# ProProject_ExtBoard-002_2024-05-18.net
KiCad netlist of a schematic drawn in EasyEDA Pro
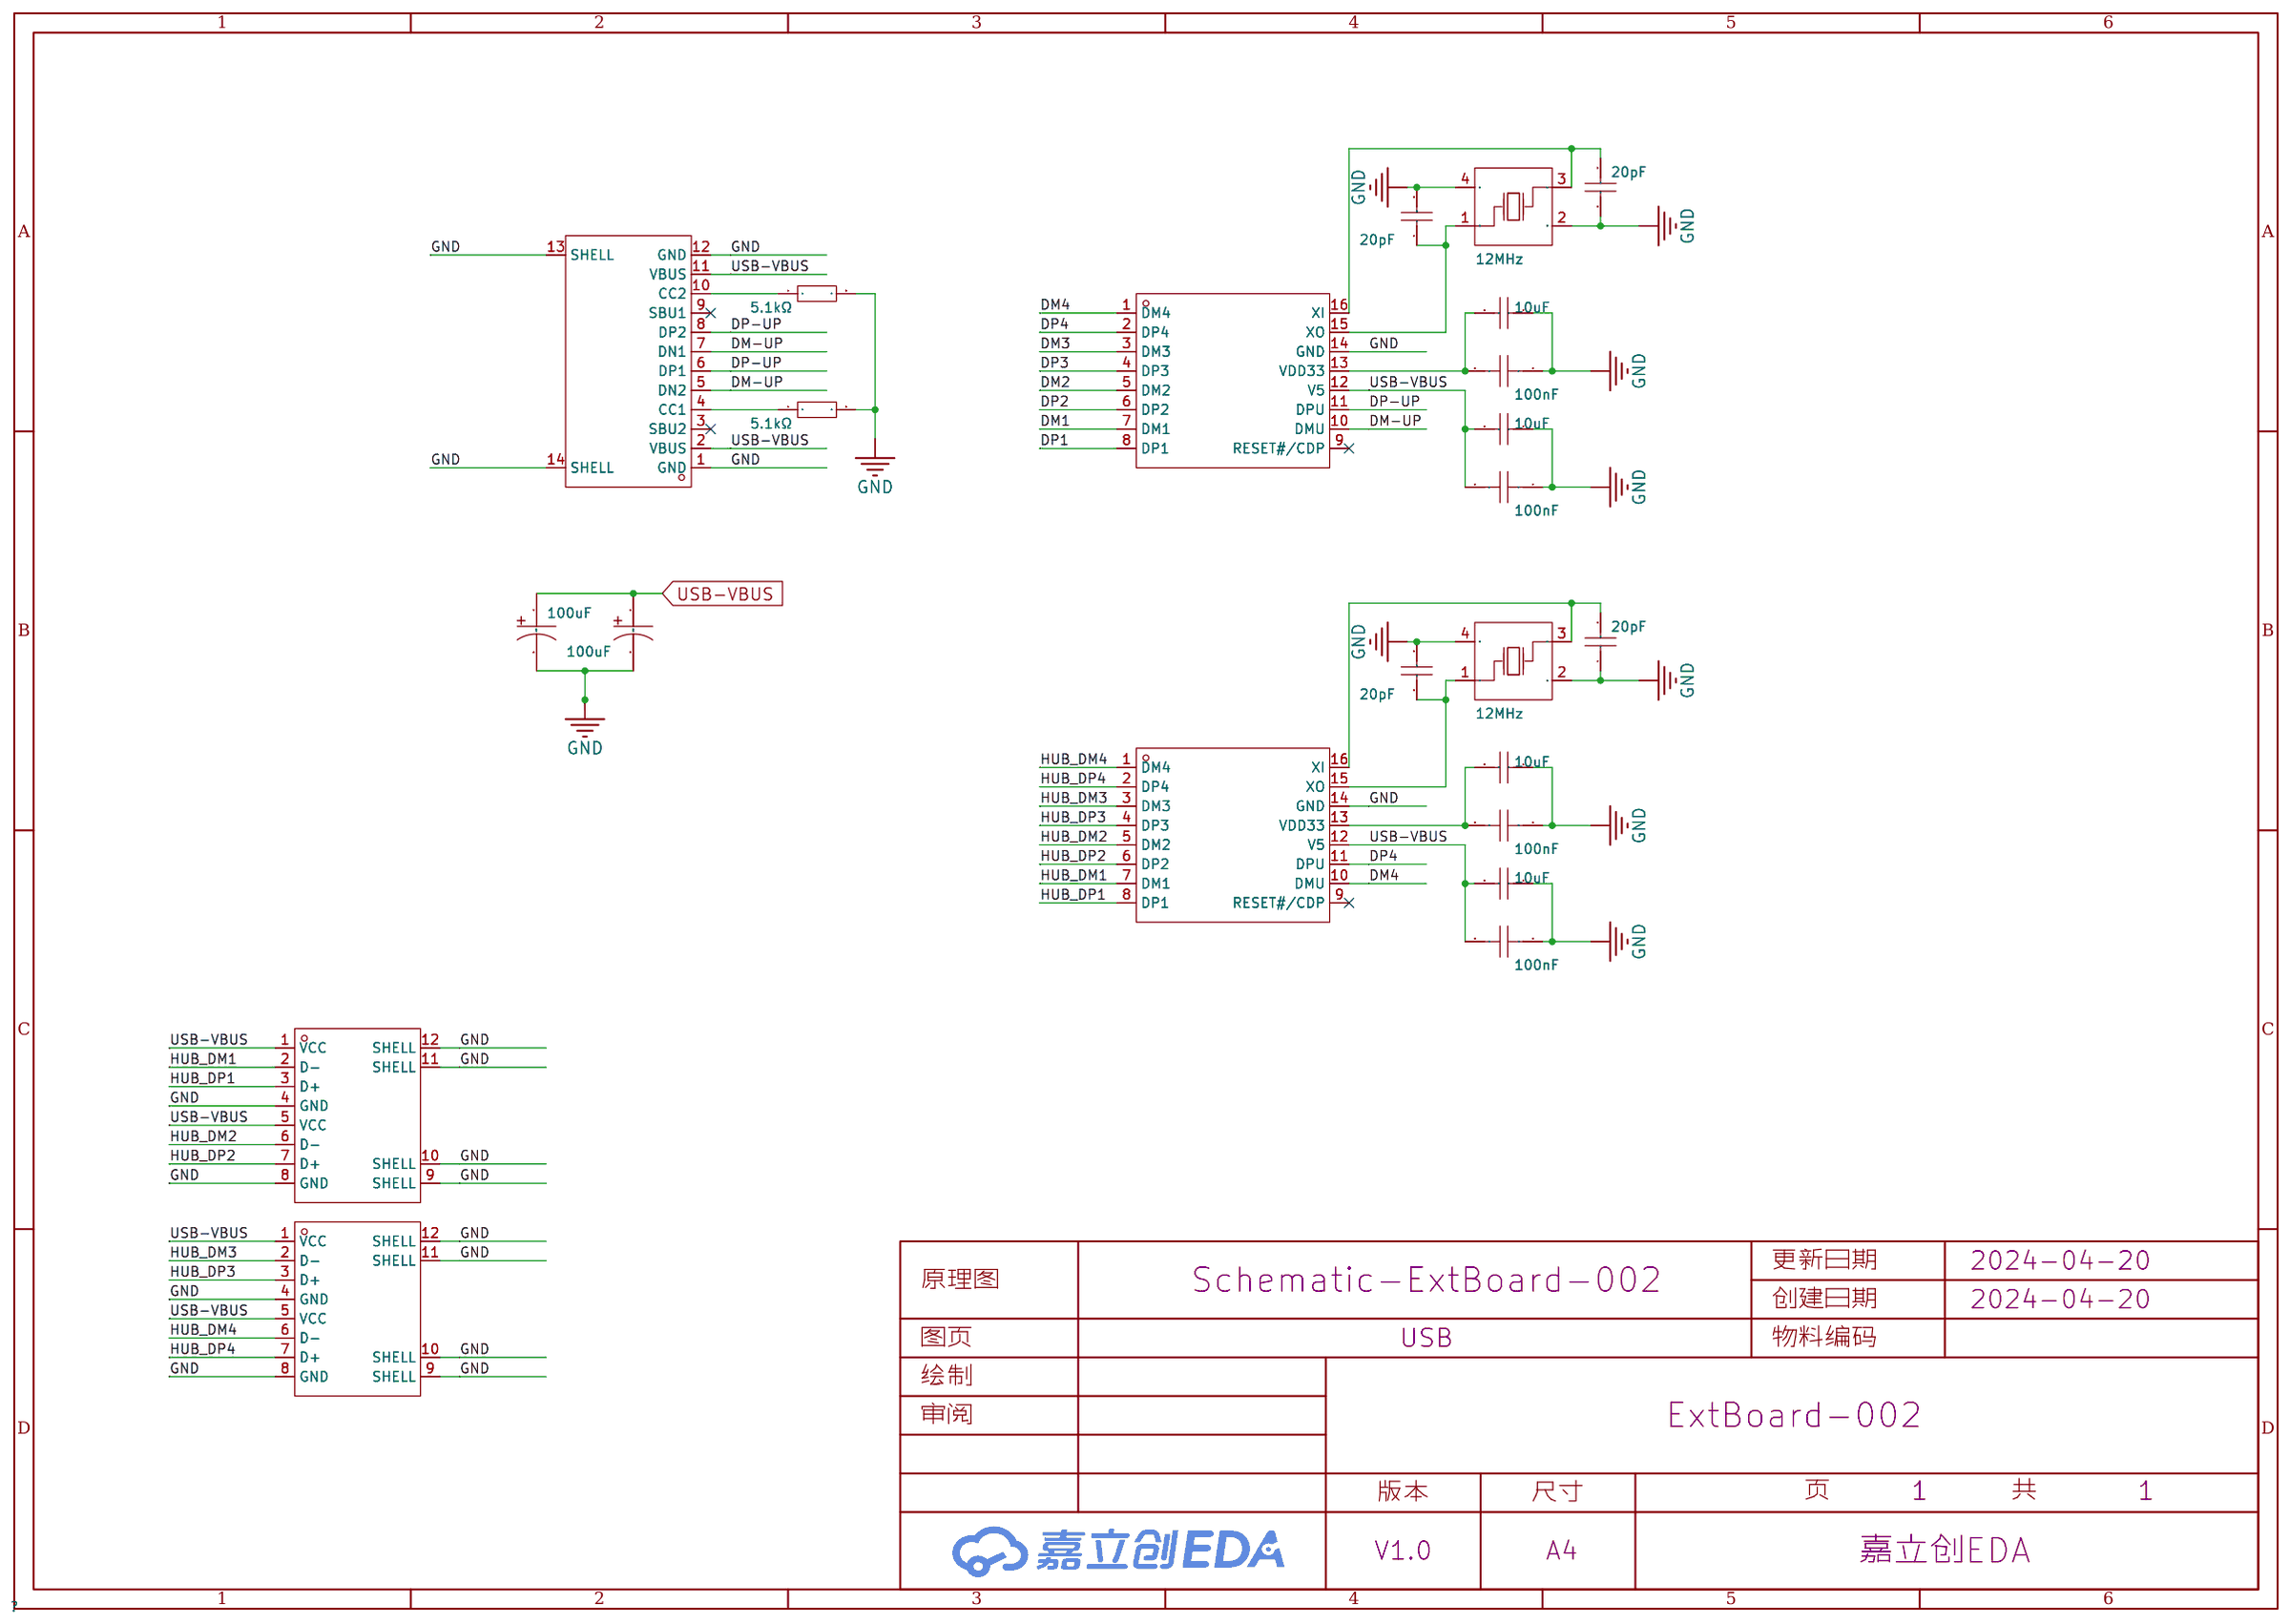
[diagram p0: USB]
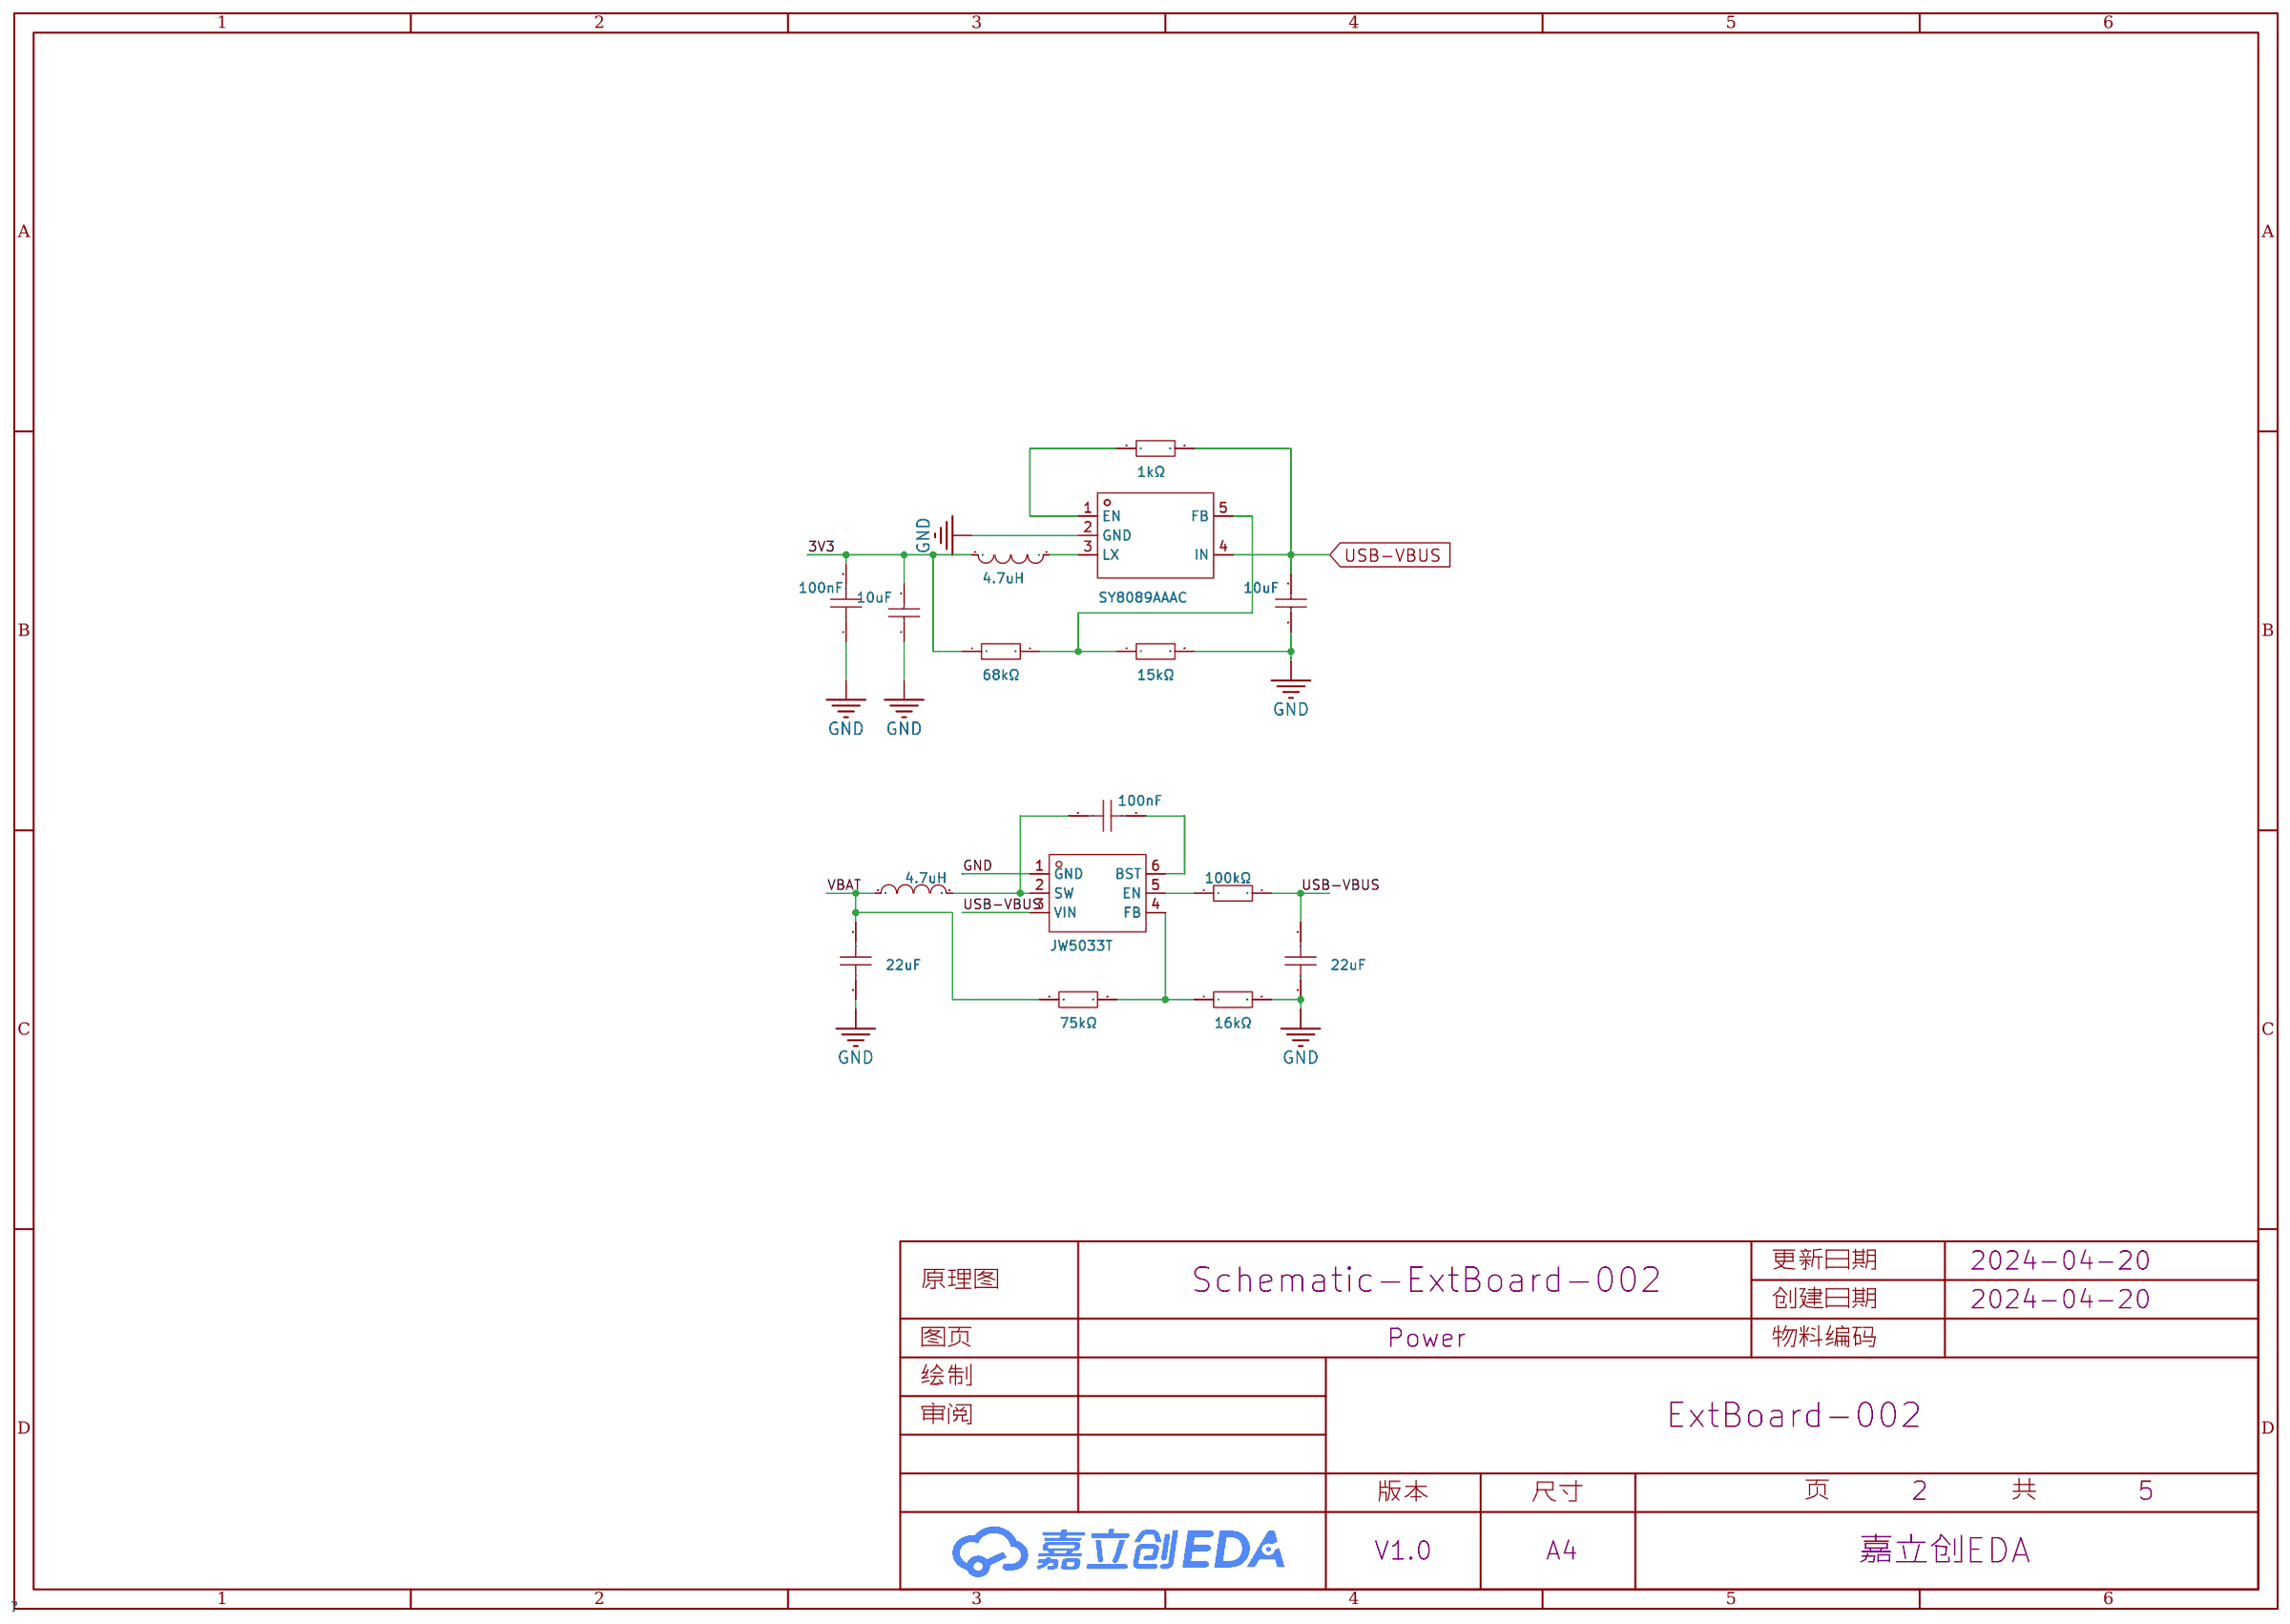
[diagram p1: Power]
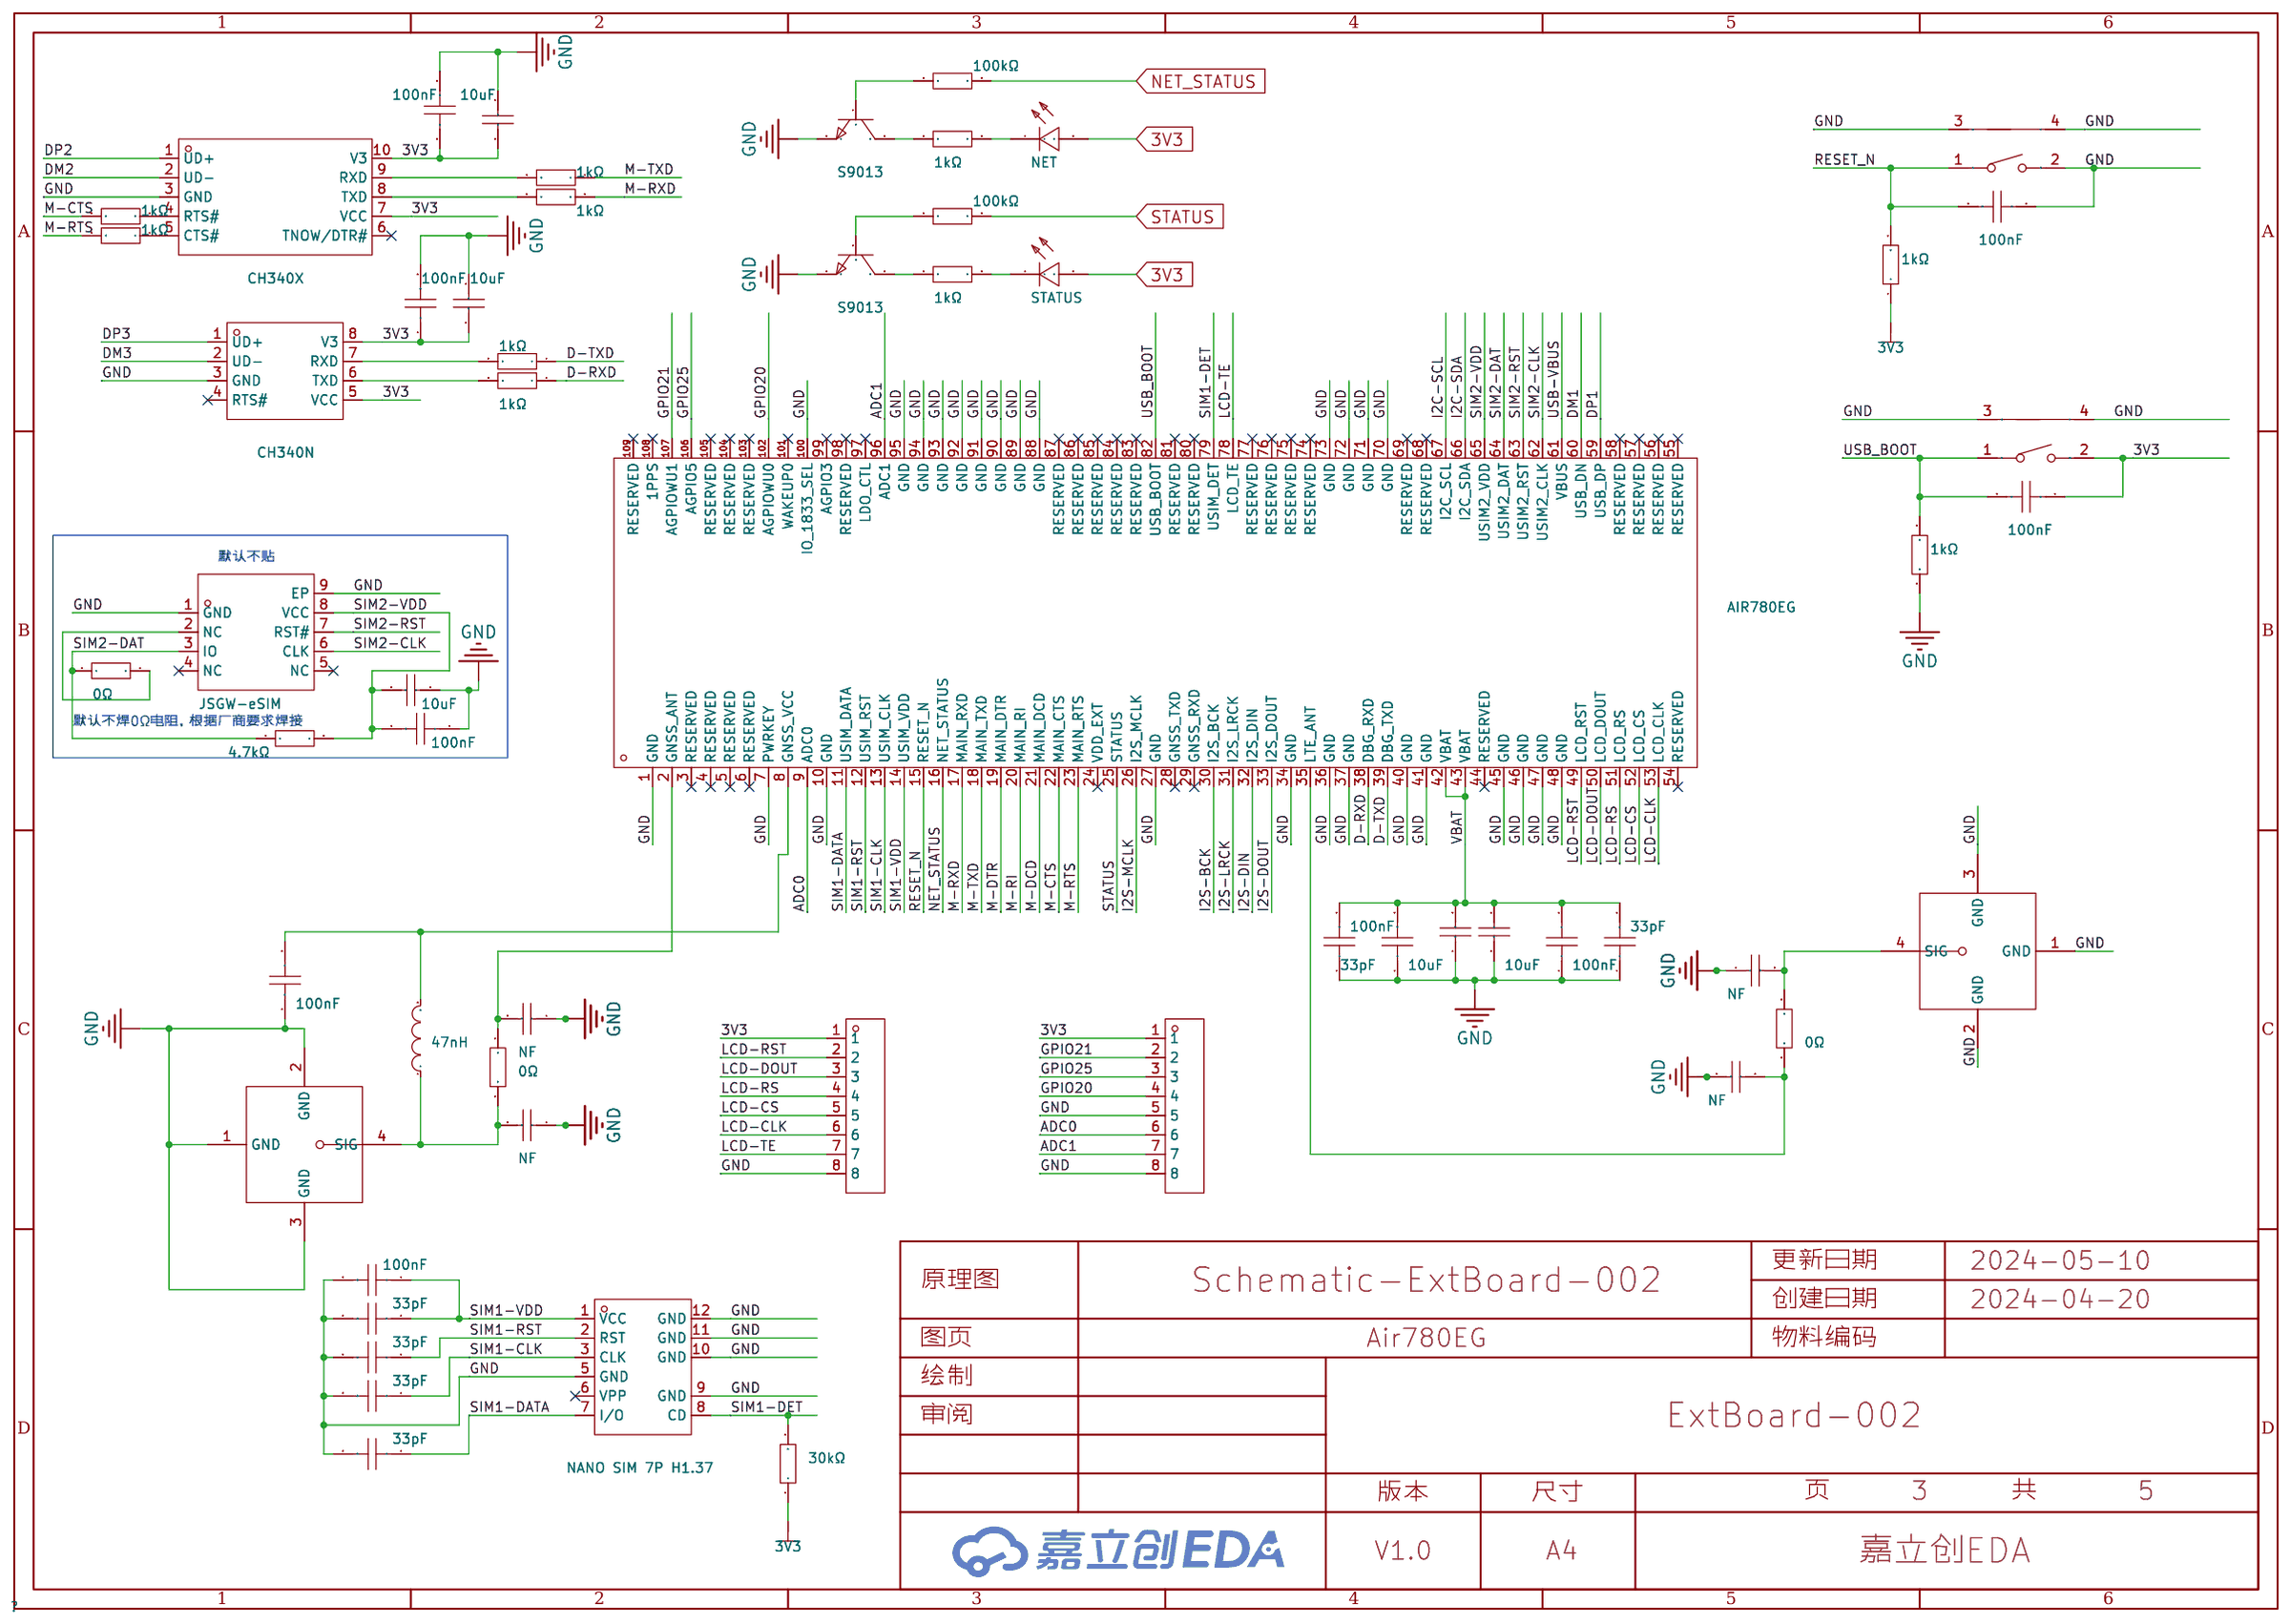
[diagram p2: Air780EG]
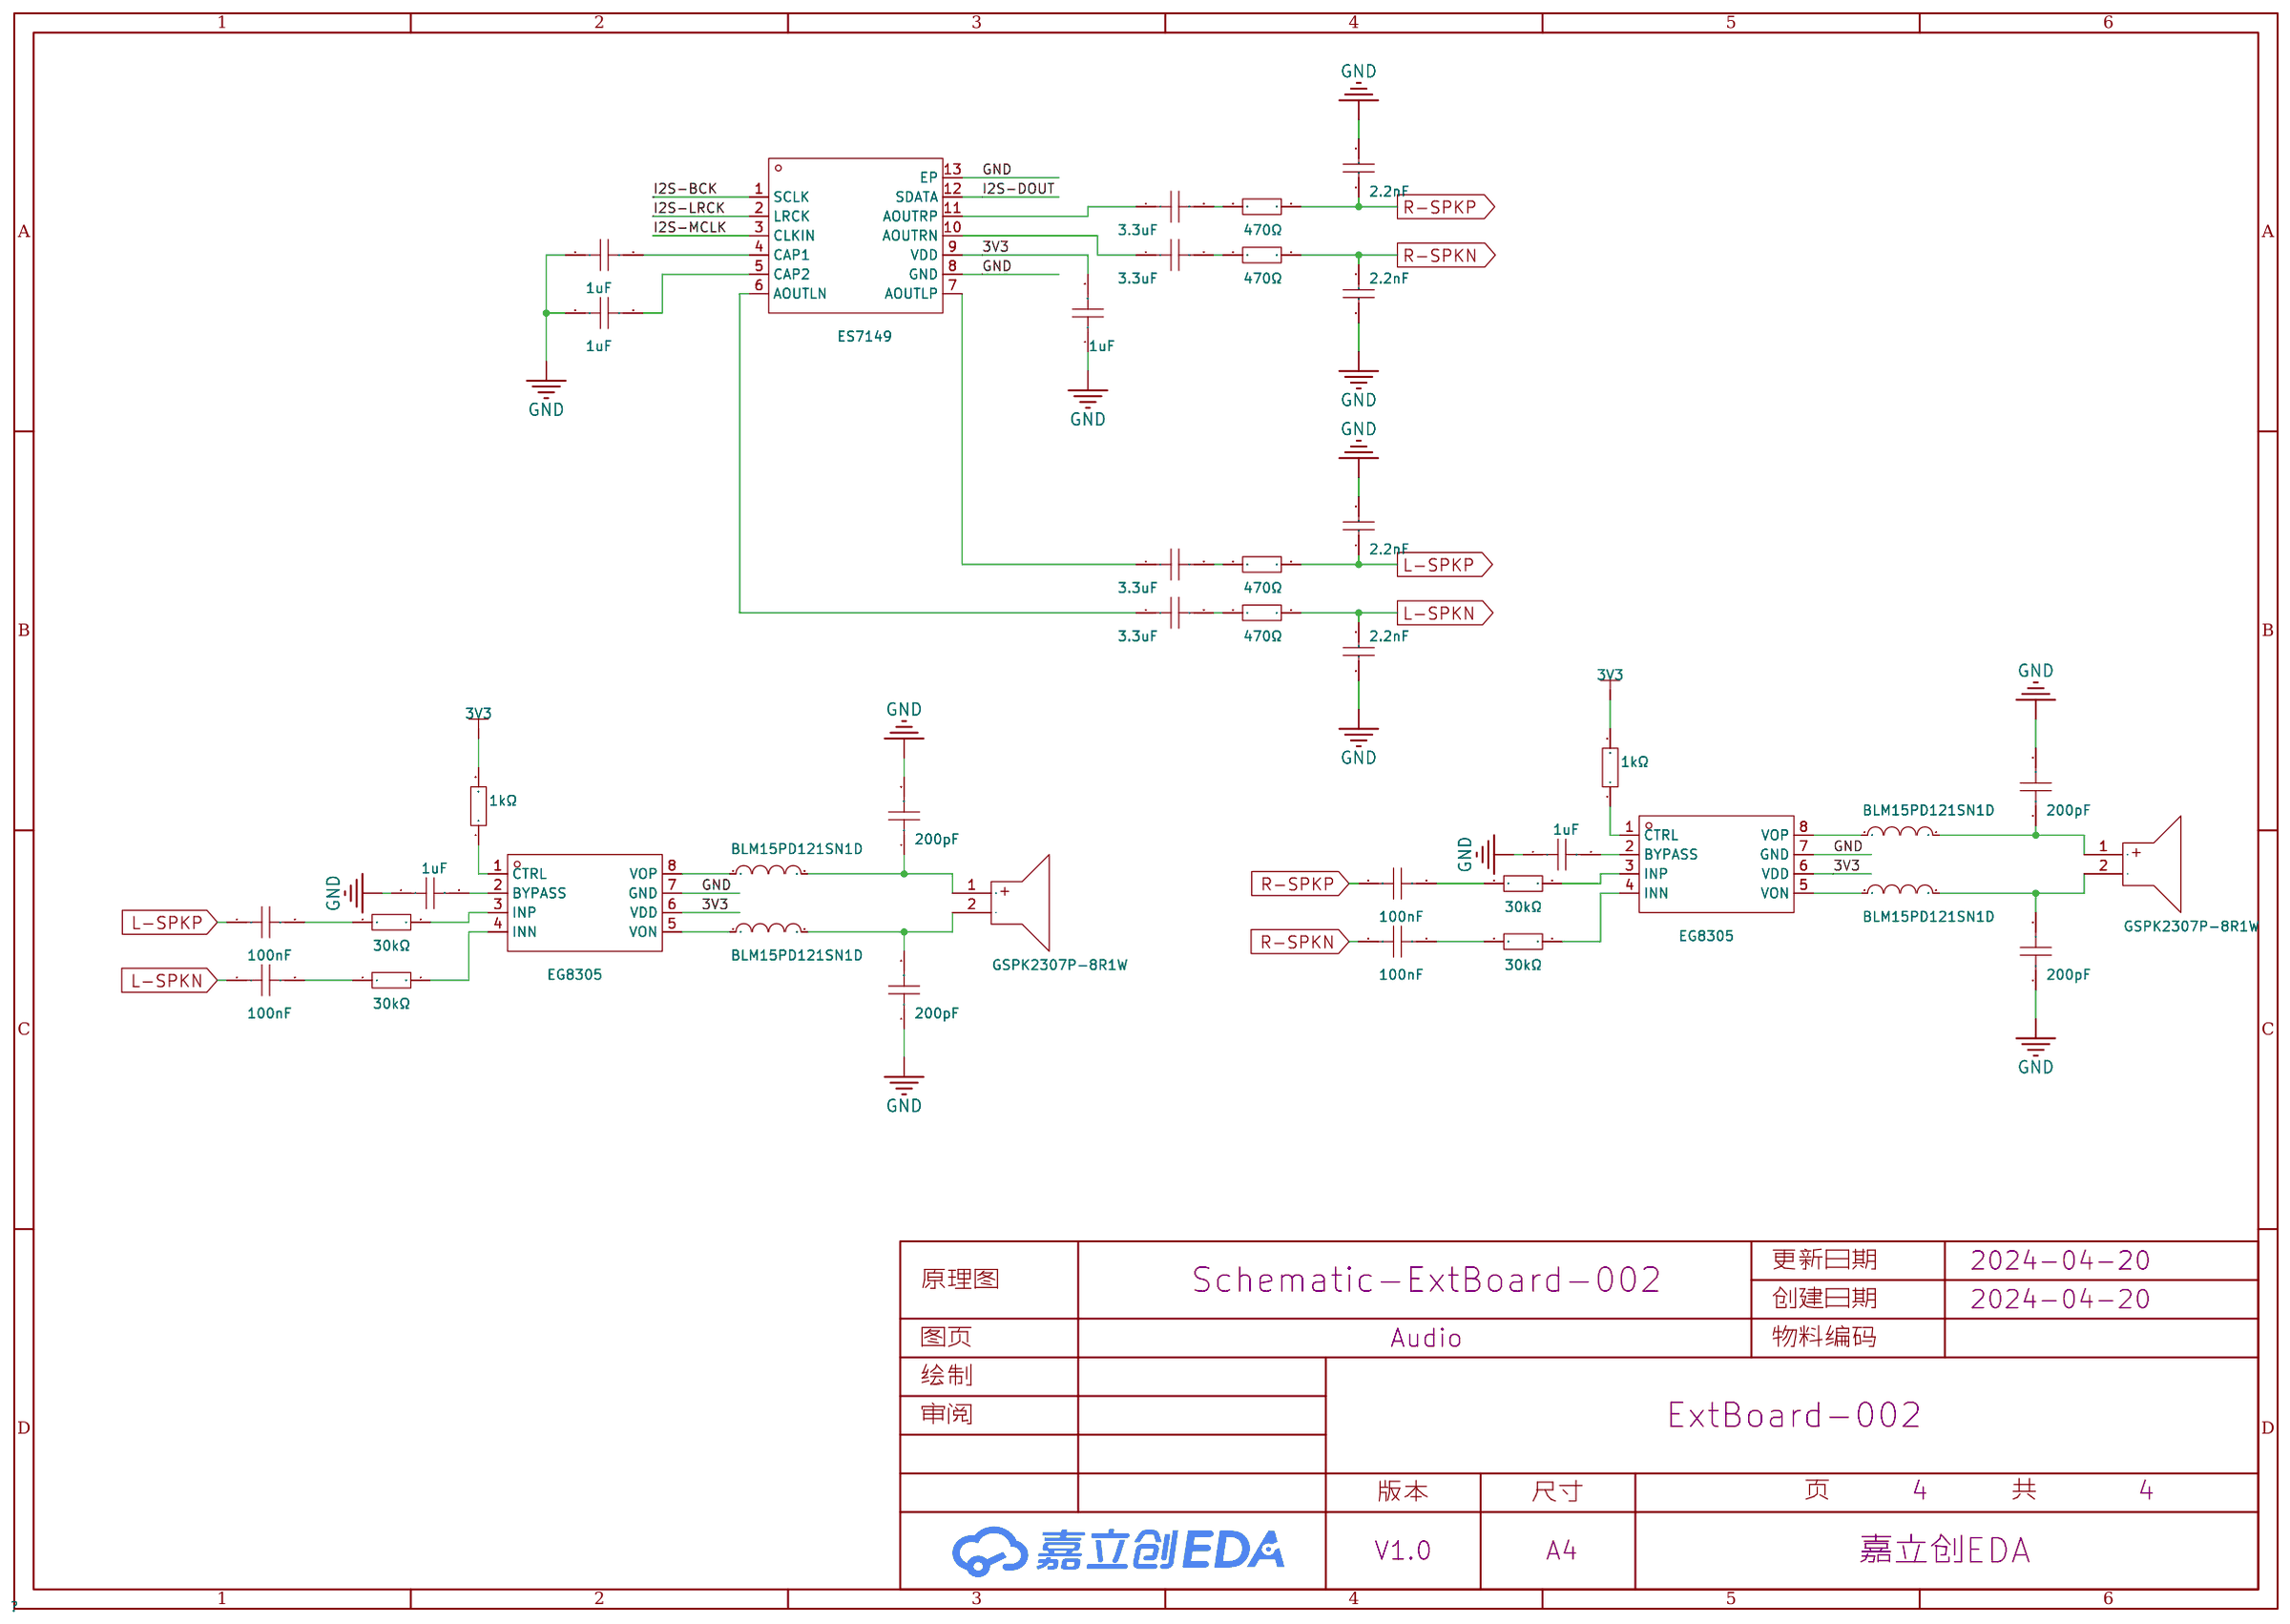
[diagram p3: Audio]
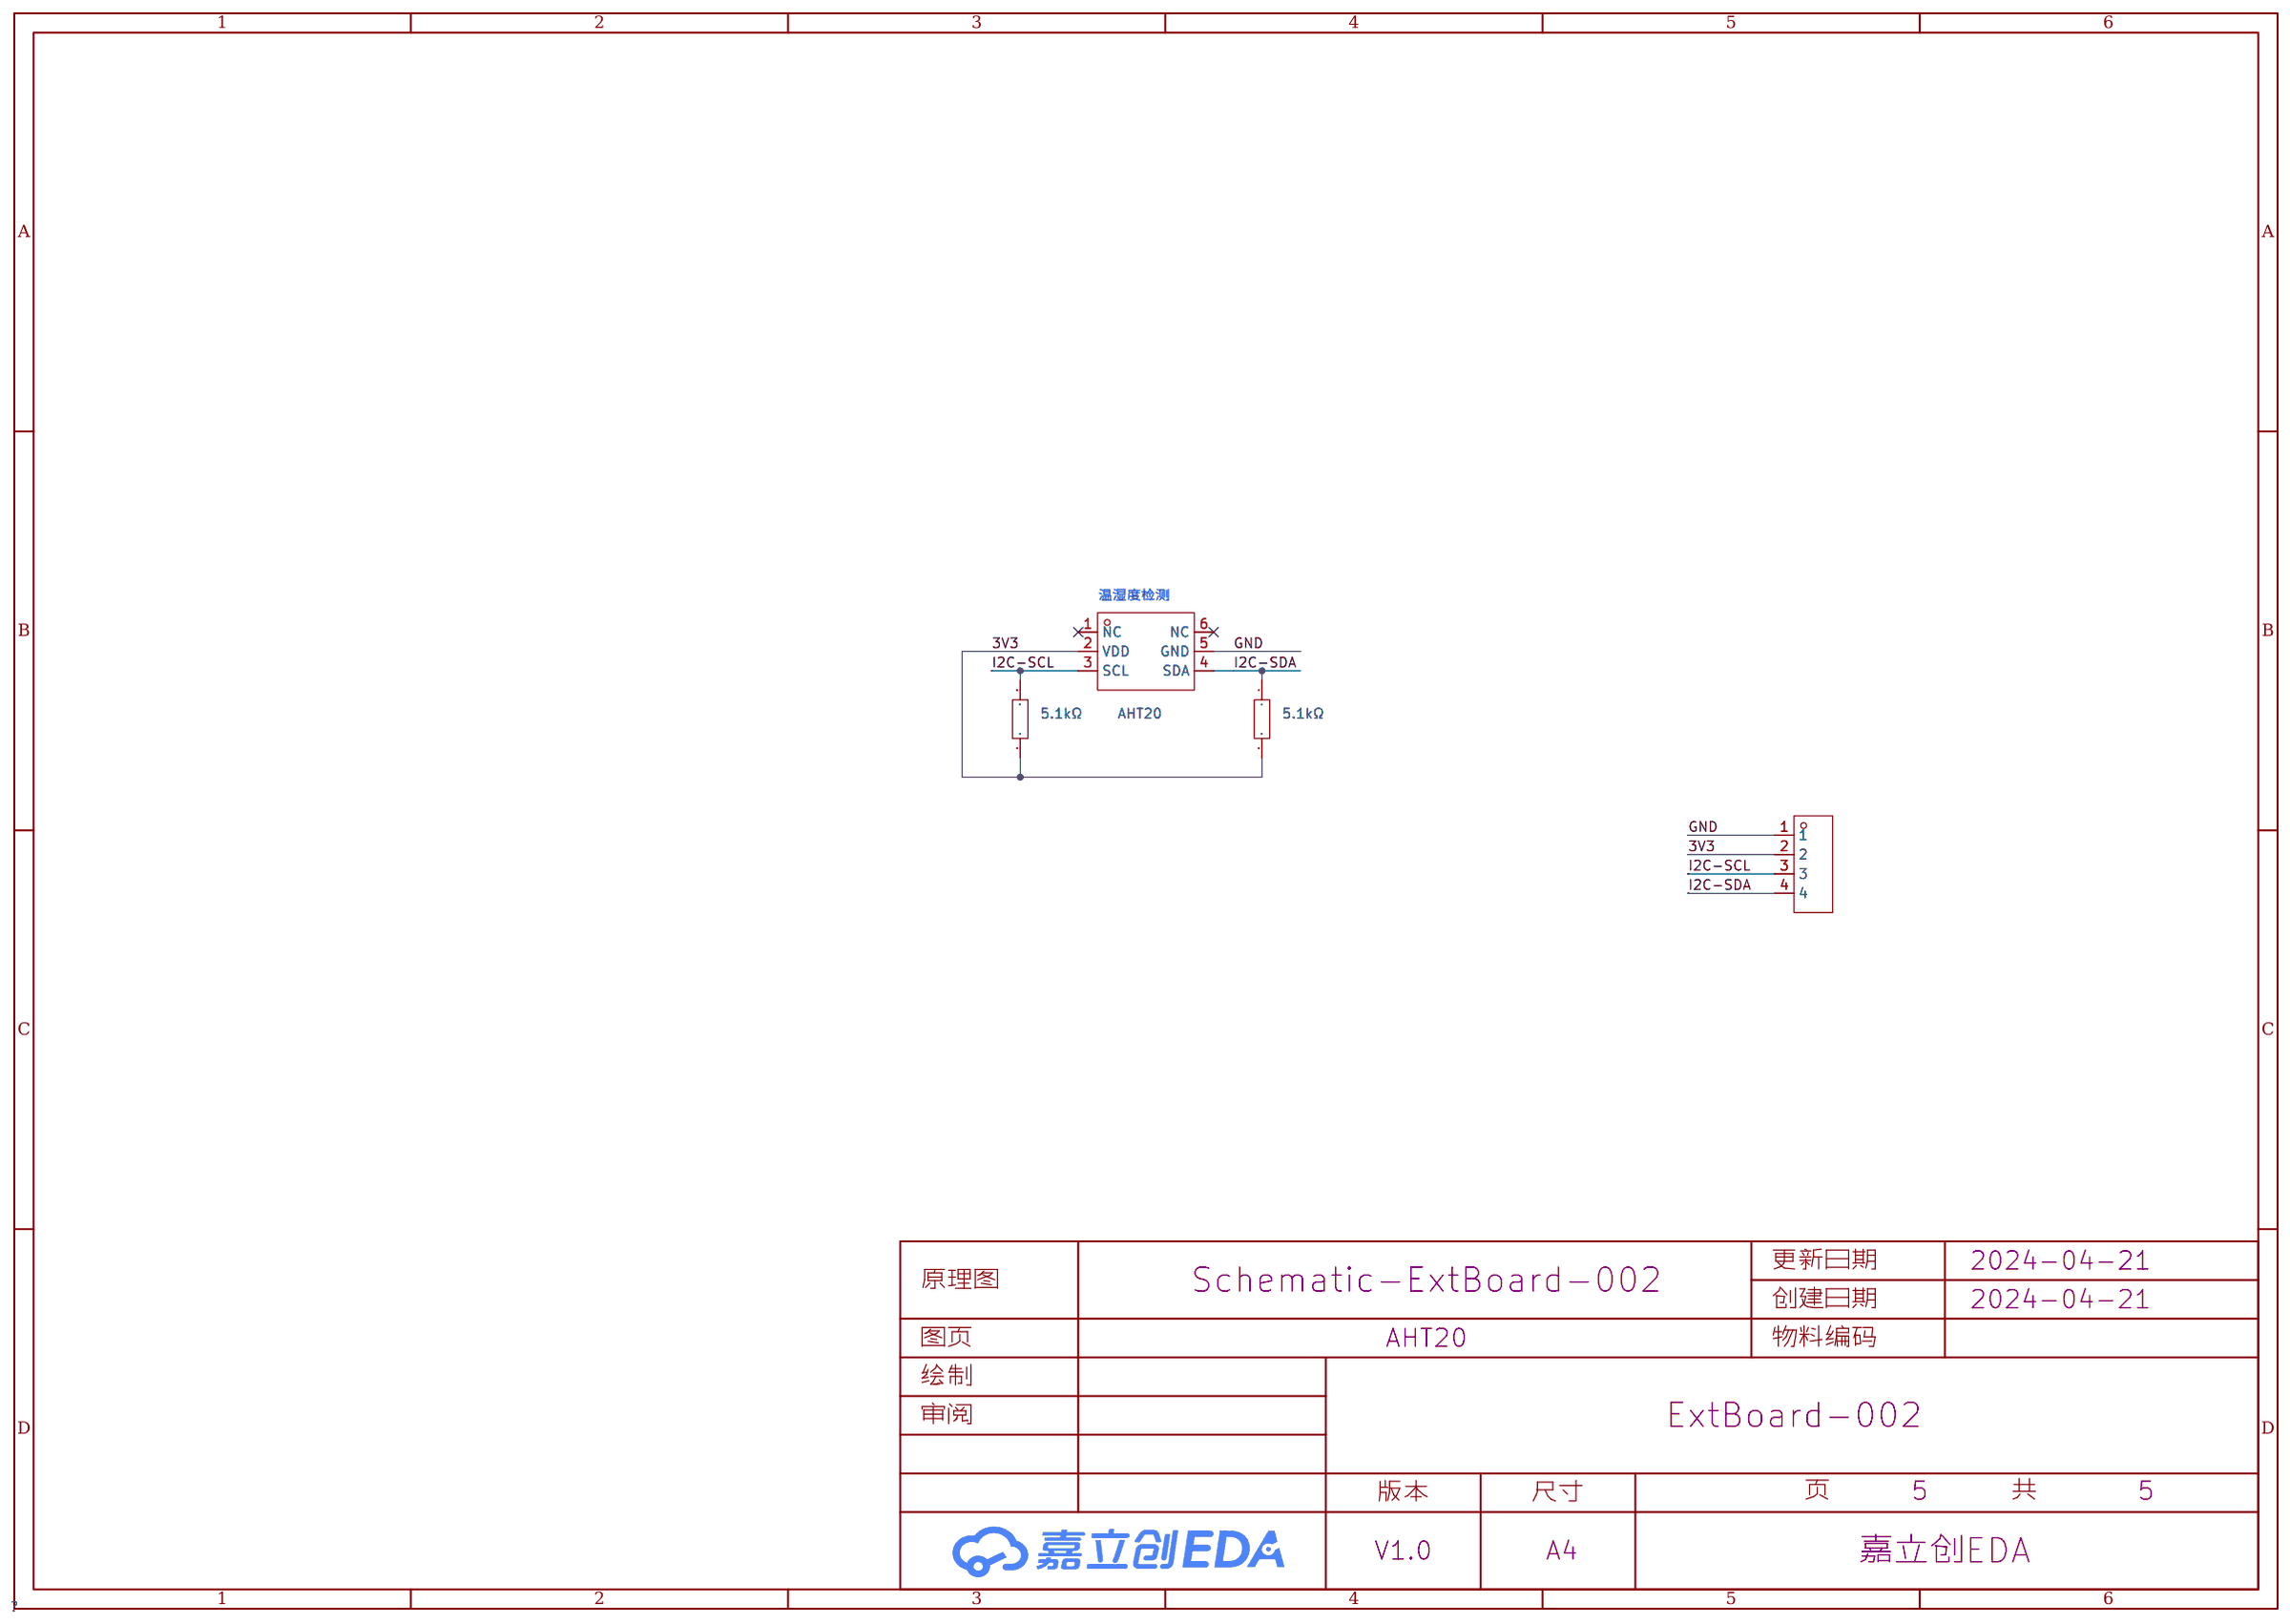
[diagram p4: AHT20]

(export (version "E")
  (design (tool "Eeschema 10.0.6"))
  (components
    (comp (ref "C1")
      (value "20pF")
      (footprint "easyedapro:C0402")
      (description "容值:20pF;精度:±5%;额定电压:50V;材质(温度系数):C0G;")
      (fields (field (name "Manufacturer Part") "0402CG200J500NT") (field (name "Manufacturer") "FH(风华)"))
      (libsource (lib "easyedapro") (part "0402CG200J500NT"))
    )
    (comp (ref "C2")
      (value "20pF")
      (footprint "easyedapro:C0402")
      (description "容值:20pF;精度:±5%;额定电压:50V;材质(温度系数):C0G;")
      (fields (field (name "Manufacturer Part") "0402CG200J500NT") (field (name "Manufacturer") "FH(风华)"))
      (libsource (lib "easyedapro") (part "0402CG200J500NT"))
    )
    (comp (ref "C3")
      (value "10uF")
      (footprint "easyedapro:C0402")
      (description "容值:10uF;精度:±20%;额定电压:6.3V;材质(温度系数):X5R;")
      (fields
        (field (name "Manufacturer Part") "CL05A106MQ5NUNC")
        (field (name "Manufacturer") "SAMSUNG(三星)")
      )
      (libsource (lib "easyedapro") (part "CL05A106MQ5NUNC"))
    )
    (comp (ref "C4")
      (value "100nF")
      (footprint "easyedapro:C0402")
      (description "容值:100nF;精度:±10%;额定电压:16V;材质(温度系数):X7R;")
      (fields
        (field (name "Manufacturer Part") "CC0402KRX7R7BB104")
        (field (name "Manufacturer") "YAGEO(国巨)")
      )
      (libsource (lib "easyedapro") (part "CC0402KRX7R7BB104"))
    )
    (comp (ref "C5")
      (value "10uF")
      (footprint "easyedapro:C0402")
      (description "容值:10uF;精度:±20%;额定电压:6.3V;材质(温度系数):X5R;")
      (fields
        (field (name "Manufacturer Part") "CL05A106MQ5NUNC")
        (field (name "Manufacturer") "SAMSUNG(三星)")
      )
      (libsource (lib "easyedapro") (part "CL05A106MQ5NUNC"))
    )
    (comp (ref "C6")
      (value "100nF")
      (footprint "easyedapro:C0402")
      (description "容值:100nF;精度:±10%;额定电压:16V;材质(温度系数):X7R;")
      (fields
        (field (name "Manufacturer Part") "CC0402KRX7R7BB104")
        (field (name "Manufacturer") "YAGEO(国巨)")
      )
      (libsource (lib "easyedapro") (part "CC0402KRX7R7BB104"))
    )
    (comp (ref "C7")
      (value "100uF")
      (footprint "easyedapro:CAP-SMD_BD6.3-L6.6-W6.6-FD")
      (description "容值:100uF;精度:±20%;额定电压:16V;纹波电流:-;等效串联电阻:-;")
      (fields (field (name "Manufacturer Part") "VEZ101M1CTR-0605") (field (name "Manufacturer") "lelon(立隆)"))
      (libsource (lib "easyedapro") (part "VEZ101M1C0605-TRO"))
    )
    (comp (ref "C8")
      (value "100uF")
      (footprint "easyedapro:CAP-SMD_BD6.3-L6.6-W6.6-FD")
      (description "容值:100uF;精度:±20%;额定电压:16V;纹波电流:-;等效串联电阻:-;")
      (fields (field (name "Manufacturer Part") "VEZ101M1CTR-0605") (field (name "Manufacturer") "lelon(立隆)"))
      (libsource (lib "easyedapro") (part "VEZ101M1C0605-TRO"))
    )
    (comp (ref "C9")
      (value "20pF")
      (footprint "easyedapro:C0402")
      (description "容值:20pF;精度:±5%;额定电压:50V;材质(温度系数):C0G;")
      (fields (field (name "Manufacturer Part") "0402CG200J500NT") (field (name "Manufacturer") "FH(风华)"))
      (libsource (lib "easyedapro") (part "0402CG200J500NT"))
    )
    (comp (ref "C10")
      (value "20pF")
      (footprint "easyedapro:C0402")
      (description "容值:20pF;精度:±5%;额定电压:50V;材质(温度系数):C0G;")
      (fields (field (name "Manufacturer Part") "0402CG200J500NT") (field (name "Manufacturer") "FH(风华)"))
      (libsource (lib "easyedapro") (part "0402CG200J500NT"))
    )
    (comp (ref "C11")
      (value "10uF")
      (footprint "easyedapro:C0402")
      (description "容值:10uF;精度:±20%;额定电压:6.3V;材质(温度系数):X5R;")
      (fields
        (field (name "Manufacturer Part") "CL05A106MQ5NUNC")
        (field (name "Manufacturer") "SAMSUNG(三星)")
      )
      (libsource (lib "easyedapro") (part "CL05A106MQ5NUNC"))
    )
    (comp (ref "C12")
      (value "100nF")
      (footprint "easyedapro:C0402")
      (description "容值:100nF;精度:±10%;额定电压:16V;材质(温度系数):X7R;")
      (fields
        (field (name "Manufacturer Part") "CC0402KRX7R7BB104")
        (field (name "Manufacturer") "YAGEO(国巨)")
      )
      (libsource (lib "easyedapro") (part "CC0402KRX7R7BB104"))
    )
    (comp (ref "C13")
      (value "10uF")
      (footprint "easyedapro:C0402")
      (description "容值:10uF;精度:±20%;额定电压:6.3V;材质(温度系数):X5R;")
      (fields
        (field (name "Manufacturer Part") "CL05A106MQ5NUNC")
        (field (name "Manufacturer") "SAMSUNG(三星)")
      )
      (libsource (lib "easyedapro") (part "CL05A106MQ5NUNC"))
    )
    (comp (ref "C14")
      (value "100nF")
      (footprint "easyedapro:C0402")
      (description "容值:100nF;精度:±10%;额定电压:16V;材质(温度系数):X7R;")
      (fields
        (field (name "Manufacturer Part") "CC0402KRX7R7BB104")
        (field (name "Manufacturer") "YAGEO(国巨)")
      )
      (libsource (lib "easyedapro") (part "CC0402KRX7R7BB104"))
    )
    (comp (ref "R1")
      (value "5.1kΩ")
      (footprint "easyedapro:R0402")
      (description "阻值:5.1kΩ;精度:±1%;功率:62.5mW;温度系数:±100ppm/°C;电阻类型:厚膜电阻;")
      (fields
        (field (name "Manufacturer Part") "0402WGF5101TCE")
        (field (name "Manufacturer") "UNI-ROYAL(厚声)")
      )
      (libsource (lib "easyedapro") (part "0402WGF5101TCE"))
    )
    (comp (ref "R2")
      (value "5.1kΩ")
      (footprint "easyedapro:R0402")
      (description "阻值:5.1kΩ;精度:±1%;功率:62.5mW;温度系数:±100ppm/°C;电阻类型:厚膜电阻;")
      (fields
        (field (name "Manufacturer Part") "0402WGF5101TCE")
        (field (name "Manufacturer") "UNI-ROYAL(厚声)")
      )
      (libsource (lib "easyedapro") (part "0402WGF5101TCE"))
    )
    (comp (ref "U1")
      (value "CH334R")
      (footprint "easyedapro:QSOP-16_L4.9-W3.9-P0.64-LS6.0-BL")
      (fields (field (name "Manufacturer") "WCH(南京沁恒)"))
      (libsource (lib "easyedapro") (part "CH334R"))
    )
    (comp (ref "U2")
      (value "CH334R")
      (footprint "easyedapro:QSOP-16_L4.9-W3.9-P0.64-LS6.0-BL")
      (fields (field (name "Manufacturer") "WCH(南京沁恒)"))
      (libsource (lib "easyedapro") (part "CH334R"))
    )
    (comp (ref "USB1")
      (value "TYPE-C 16PIN 2MD(073)")
      (footprint "easyedapro:USB-C-SMD_TYPE-C-6PIN-2MD-073")
      (description "连接器类型:Type-C;标准:-;公母:母;端口数量:1;触点数量:16P;安装方式:卧贴;额定电流 - 电源:5A;工作温度范围:-25°C~+85°C;")
      (fields (field (name "Manufacturer") "SHOU HAN(首韩)"))
      (libsource (lib "easyedapro") (part "TYPE-C 16PIN 2MD(073)"))
    )
    (comp (ref "USB2")
      (value "AF SS-JB17.6")
      (footprint "easyedapro:USB-A-TH_AF-SS-JB17.6")
      (description "连接器类型:Type-A;标准:USB 2.0;公母:母;端口数量:2;触点数量:4P+4P;安装方式:弯插;额定电流 - 电源:1.5A;工作温度范围:-25°C~+85°C;")
      (fields (field (name "Manufacturer") "SHOU HAN(首韩)"))
      (libsource (lib "easyedapro") (part "AF SS-JB17.6"))
    )
    (comp (ref "USB3")
      (value "AF SS-JB17.6")
      (footprint "easyedapro:USB-A-TH_AF-SS-JB17.6")
      (description "连接器类型:Type-A;标准:USB 2.0;公母:母;端口数量:2;触点数量:4P+4P;安装方式:弯插;额定电流 - 电源:1.5A;工作温度范围:-25°C~+85°C;")
      (fields (field (name "Manufacturer") "SHOU HAN(首韩)"))
      (libsource (lib "easyedapro") (part "AF SS-JB17.6"))
    )
    (comp (ref "X1")
      (value "12MHz")
      (footprint "easyedapro:OSC-SMD_4P-L3.2-W2.5-BL")
      (description "晶振类型:贴片晶振;频率:12MHz;常温频差:±10ppm;外接负载电容:20pF;频率稳定度(全温):±30ppm;")
      (fields (field (name "Manufacturer Part") "X322512MSB4SI") (field (name "Manufacturer") "YXC(扬兴晶振)"))
      (libsource (lib "easyedapro") (part "X322512MSB4SI"))
    )
    (comp (ref "X2")
      (value "12MHz")
      (footprint "easyedapro:OSC-SMD_4P-L3.2-W2.5-BL")
      (description "晶振类型:贴片晶振;频率:12MHz;常温频差:±10ppm;外接负载电容:20pF;频率稳定度(全温):±30ppm;")
      (fields (field (name "Manufacturer Part") "X322512MSB4SI") (field (name "Manufacturer") "YXC(扬兴晶振)"))
      (libsource (lib "easyedapro") (part "X322512MSB4SI"))
    )
    (comp (ref "C15")
      (value "100nF")
      (footprint "easyedapro:C0402")
      (description "容值:100nF;精度:±10%;额定电压:16V;材质(温度系数):X7R;")
      (fields
        (field (name "Manufacturer Part") "CC0402KRX7R7BB104")
        (field (name "Manufacturer") "YAGEO(国巨)")
      )
      (libsource (lib "easyedapro") (part "CC0402KRX7R7BB104"))
    )
    (comp (ref "C16")
      (value "10uF")
      (footprint "easyedapro:C0402")
      (description "容值:10uF;精度:±20%;额定电压:6.3V;材质(温度系数):X5R;")
      (fields
        (field (name "Manufacturer Part") "CL05A106MQ5NUNC")
        (field (name "Manufacturer") "SAMSUNG(三星)")
      )
      (libsource (lib "easyedapro") (part "CL05A106MQ5NUNC"))
    )
    (comp (ref "C17")
      (value "10uF")
      (footprint "easyedapro:C0402")
      (description "容值:10uF;精度:±20%;额定电压:6.3V;材质(温度系数):X5R;")
      (fields
        (field (name "Manufacturer Part") "CL05A106MQ5NUNC")
        (field (name "Manufacturer") "SAMSUNG(三星)")
      )
      (libsource (lib "easyedapro") (part "CL05A106MQ5NUNC"))
    )
    (comp (ref "C18")
      (value "100nF")
      (footprint "easyedapro:C0402")
      (description "容值:100nF;精度:±10%;额定电压:16V;材质(温度系数):X7R;")
      (fields
        (field (name "Manufacturer Part") "CC0402KRX7R7BB104")
        (field (name "Manufacturer") "YAGEO(国巨)")
      )
      (libsource (lib "easyedapro") (part "CC0402KRX7R7BB104"))
    )
    (comp (ref "C19")
      (value "22uF")
      (footprint "easyedapro:C0603")
      (description "容值:22uF;精度:±20%;额定电压:16V;材质(温度系数):X5R;")
      (fields
        (field (name "Manufacturer Part") "CL10A226MO7JZNC")
        (field (name "Manufacturer") "SAMSUNG(三星)")
      )
      (libsource (lib "easyedapro") (part "CL10A226MO7JZNC"))
    )
    (comp (ref "C20")
      (value "22uF")
      (footprint "easyedapro:C0603")
      (description "容值:22uF;精度:±20%;额定电压:16V;材质(温度系数):X5R;")
      (fields
        (field (name "Manufacturer Part") "CL10A226MO7JZNC")
        (field (name "Manufacturer") "SAMSUNG(三星)")
      )
      (libsource (lib "easyedapro") (part "CL10A226MO7JZNC"))
    )
    (comp (ref "L1")
      (value "4.7uH")
      (footprint "easyedapro:IND-SMD_L4.0-W4.0")
      (description "直流电阻(DCR):78mΩ;精度:±20%;电感值:4.7uH;额定电流:2A;")
      (fields (field (name "Manufacturer Part") "SWPA4030S4R7MT") (field (name "Manufacturer") "Sunlord(顺络)"))
      (libsource (lib "easyedapro") (part "SWPA4030S4R7MT"))
    )
    (comp (ref "L2")
      (value "4.7uH")
      (footprint "easyedapro:IND-SMD_L4.0-W4.0")
      (description "直流电阻(DCR):78mΩ;精度:±20%;电感值:4.7uH;额定电流:2A;")
      (fields (field (name "Manufacturer Part") "SWPA4030S4R7MT") (field (name "Manufacturer") "Sunlord(顺络)"))
      (libsource (lib "easyedapro") (part "SWPA4030S4R7MT"))
    )
    (comp (ref "R3")
      (value "1kΩ")
      (footprint "easyedapro:R0402")
      (description "阻值:1kΩ;精度:±1%;功率:62.5mW;温度系数:±100ppm/°C;电阻类型:厚膜电阻;")
      (fields
        (field (name "Manufacturer Part") "0402WGF1001TCE")
        (field (name "Manufacturer") "UNI-ROYAL(厚声)")
      )
      (libsource (lib "easyedapro") (part "0402WGF1001TCE"))
    )
    (comp (ref "R4")
      (value "68kΩ")
      (footprint "easyedapro:R0402")
      (description "阻值:68kΩ;精度:±1%;功率:62.5mW;温度系数:±100ppm/°C;电阻类型:厚膜电阻;")
      (fields
        (field (name "Manufacturer Part") "0402WGF6802TCE")
        (field (name "Manufacturer") "UNI-ROYAL(厚声)")
      )
      (libsource (lib "easyedapro") (part "0402WGF6802TCE"))
    )
    (comp (ref "R5")
      (value "15kΩ")
      (footprint "easyedapro:R0402")
      (description "阻值:15kΩ;精度:±1%;功率:62.5mW;温度系数:±100ppm/°C;电阻类型:厚膜电阻;")
      (fields
        (field (name "Manufacturer Part") "0402WGF1502TCE")
        (field (name "Manufacturer") "UNI-ROYAL(厚声)")
      )
      (libsource (lib "easyedapro") (part "0402WGF1502TCE"))
    )
    (comp (ref "R6")
      (value "100kΩ")
      (footprint "easyedapro:R0402")
      (description "电阻类型:厚膜电阻;阻值:100kΩ;精度:±1%;功率:62.5mW;")
      (fields (field (name "Manufacturer Part") "RC0402FR-07100KL") (field (name "Manufacturer") "YAGEO(国巨)"))
      (libsource (lib "easyedapro") (part "RC0402FR-07100KL"))
    )
    (comp (ref "R7")
      (value "75kΩ")
      (footprint "easyedapro:R0402")
      (description "电阻类型:厚膜电阻;阻值:75kΩ;功率:63mW;温度系数:±100ppm/°C;精度:±1%;")
      (fields (field (name "Manufacturer Part") "AECR0402F75K0K9") (field (name "Manufacturer") "RESI(开步睿思）"))
      (libsource (lib "easyedapro") (part "AECR0402F75K0K9"))
    )
    (comp (ref "R8")
      (value "16kΩ")
      (footprint "easyedapro:R0402")
      (description "阻值:16kΩ;精度:±1%;功率:62.5mW;温度系数:±100ppm/°C;电阻类型:厚膜电阻;")
      (fields
        (field (name "Manufacturer Part") "0402WGF1602TCE")
        (field (name "Manufacturer") "UNI-ROYAL(厚声)")
      )
      (libsource (lib "easyedapro") (part "0402WGF1602TCE"))
    )
    (comp (ref "U3")
      (value "SY8089AAAC")
      (footprint "easyedapro:SOT-23-5_L3.0-W1.7-P0.95-LS2.8-BR")
      (description "功能类型:降压型;同步整流:-;输出通道数:-;拓扑结构:-;输入电压:-;输出电流(最大值):-;开关频率:-;")
      (fields (field (name "Manufacturer") "silergy(矽力杰)"))
      (libsource (lib "easyedapro") (part "SY8089AAAC"))
    )
    (comp (ref "U5")
      (value "JW5033T")
      (footprint "easyedapro:TSOT-23-6_L2.9-W1.6-P0.95-LS2.8-BR")
      (description "vin=3.7V-18V")
      (fields (field (name "Manufacturer") "Joulwatt(杰华特)"))
      (libsource (lib "easyedapro") (part "JW5033T"))
    )
    (comp (ref "C21")
      (value "100nF")
      (footprint "easyedapro:C0402")
      (description "容值:100nF;精度:±10%;额定电压:16V;材质(温度系数):X7R;")
      (fields
        (field (name "Manufacturer Part") "CC0402KRX7R7BB104")
        (field (name "Manufacturer") "YAGEO(国巨)")
      )
      (libsource (lib "easyedapro") (part "CC0402KRX7R7BB104"))
    )
    (comp (ref "C22")
      (value "10uF")
      (footprint "easyedapro:C0402")
      (description "容值:10uF;精度:±20%;额定电压:6.3V;材质(温度系数):X5R;")
      (fields
        (field (name "Manufacturer Part") "CL05A106MQ5NUNC")
        (field (name "Manufacturer") "SAMSUNG(三星)")
      )
      (libsource (lib "easyedapro") (part "CL05A106MQ5NUNC"))
    )
    (comp (ref "C23")
      (value "100nF")
      (footprint "easyedapro:C0402")
      (description "容值:100nF;精度:±10%;额定电压:16V;材质(温度系数):X7R;")
      (fields
        (field (name "Manufacturer Part") "CC0402KRX7R7BB104")
        (field (name "Manufacturer") "YAGEO(国巨)")
      )
      (libsource (lib "easyedapro") (part "CC0402KRX7R7BB104"))
    )
    (comp (ref "C24")
      (value "100nF")
      (footprint "easyedapro:C0402")
      (description "容值:100nF;精度:±10%;额定电压:16V;材质(温度系数):X7R;")
      (fields
        (field (name "Manufacturer Part") "CC0402KRX7R7BB104")
        (field (name "Manufacturer") "YAGEO(国巨)")
      )
      (libsource (lib "easyedapro") (part "CC0402KRX7R7BB104"))
    )
    (comp (ref "C25")
      (value "33pF")
      (footprint "easyedapro:C0402")
      (description "容值:33pF;精度:±5%;额定电压:50V;材质(温度系数):C0G;")
      (fields (field (name "Manufacturer Part") "C1005C0G1H330J050BA") (field (name "Manufacturer") "TDK"))
      (libsource (lib "easyedapro") (part "C1005C0G1H330J050BA"))
    )
    (comp (ref "C26")
      (value "100nF")
      (footprint "easyedapro:C0402")
      (description "容值:100nF;精度:±10%;额定电压:16V;材质(温度系数):X7R;")
      (fields
        (field (name "Manufacturer Part") "CC0402KRX7R7BB104")
        (field (name "Manufacturer") "YAGEO(国巨)")
      )
      (libsource (lib "easyedapro") (part "CC0402KRX7R7BB104"))
    )
    (comp (ref "C27")
      (value "10uF")
      (footprint "easyedapro:C0402")
      (description "容值:10uF;精度:±20%;额定电压:6.3V;材质(温度系数):X5R;")
      (fields
        (field (name "Manufacturer Part") "CL05A106MQ5NUNC")
        (field (name "Manufacturer") "SAMSUNG(三星)")
      )
      (libsource (lib "easyedapro") (part "CL05A106MQ5NUNC"))
    )
    (comp (ref "C28")
      (value "10uF")
      (footprint "easyedapro:C0402")
      (description "容值:10uF;精度:±20%;额定电压:6.3V;材质(温度系数):X5R;")
      (fields
        (field (name "Manufacturer Part") "CL05A106MQ5NUNC")
        (field (name "Manufacturer") "SAMSUNG(三星)")
      )
      (libsource (lib "easyedapro") (part "CL05A106MQ5NUNC"))
    )
    (comp (ref "C29")
      (value "100nF")
      (footprint "easyedapro:C0402")
      (description "容值:100nF;精度:±10%;额定电压:16V;材质(温度系数):X7R;")
      (fields
        (field (name "Manufacturer Part") "CC0402KRX7R7BB104")
        (field (name "Manufacturer") "YAGEO(国巨)")
      )
      (libsource (lib "easyedapro") (part "CC0402KRX7R7BB104"))
    )
    (comp (ref "C30")
      (value "33pF")
      (footprint "easyedapro:C0402")
      (description "容值:33pF;精度:±5%;额定电压:50V;材质(温度系数):C0G;")
      (fields (field (name "Manufacturer Part") "C1005C0G1H330J050BA") (field (name "Manufacturer") "TDK"))
      (libsource (lib "easyedapro") (part "C1005C0G1H330J050BA"))
    )
    (comp (ref "C31")
      (value "NF")
      (footprint "easyedapro:C0402")
      (description "容值:1pF;额定电压:50V;材质(温度系数):C0G;")
      (fields (field (name "Manufacturer Part") "0402CG1R0C500NT") (field (name "Manufacturer") "FH(风华)"))
      (libsource (lib "easyedapro") (part "0402CG1R0C500NT"))
    )
    (comp (ref "C32")
      (value "NF")
      (footprint "easyedapro:C0402")
      (description "容值:1pF;额定电压:50V;材质(温度系数):C0G;")
      (fields (field (name "Manufacturer Part") "0402CG1R0C500NT") (field (name "Manufacturer") "FH(风华)"))
      (libsource (lib "easyedapro") (part "0402CG1R0C500NT"))
    )
    (comp (ref "C33")
      (value "NF")
      (footprint "easyedapro:C0402")
      (description "容值:1pF;额定电压:50V;材质(温度系数):C0G;")
      (fields (field (name "Manufacturer Part") "0402CG1R0C500NT") (field (name "Manufacturer") "FH(风华)"))
      (libsource (lib "easyedapro") (part "0402CG1R0C500NT"))
    )
    (comp (ref "C34")
      (value "NF")
      (footprint "easyedapro:C0402")
      (description "容值:1pF;额定电压:50V;材质(温度系数):C0G;")
      (fields (field (name "Manufacturer Part") "0402CG1R0C500NT") (field (name "Manufacturer") "FH(风华)"))
      (libsource (lib "easyedapro") (part "0402CG1R0C500NT"))
    )
    (comp (ref "C35")
      (value "10uF")
      (footprint "easyedapro:C0402")
      (description "容值:10uF;精度:±20%;额定电压:6.3V;材质(温度系数):X5R;")
      (fields
        (field (name "Manufacturer Part") "CL05A106MQ5NUNC")
        (field (name "Manufacturer") "SAMSUNG(三星)")
      )
      (libsource (lib "easyedapro") (part "CL05A106MQ5NUNC"))
    )
    (comp (ref "C36")
      (value "100nF")
      (footprint "easyedapro:C0402")
      (description "容值:100nF;精度:±10%;额定电压:16V;材质(温度系数):X7R;")
      (fields
        (field (name "Manufacturer Part") "CC0402KRX7R7BB104")
        (field (name "Manufacturer") "YAGEO(国巨)")
      )
      (libsource (lib "easyedapro") (part "CC0402KRX7R7BB104"))
    )
    (comp (ref "C37")
      (value "10uF")
      (footprint "easyedapro:C0402")
      (description "容值:10uF;精度:±20%;额定电压:6.3V;材质(温度系数):X5R;")
      (fields
        (field (name "Manufacturer Part") "CL05A106MQ5NUNC")
        (field (name "Manufacturer") "SAMSUNG(三星)")
      )
      (libsource (lib "easyedapro") (part "CL05A106MQ5NUNC"))
    )
    (comp (ref "C38")
      (value "100nF")
      (footprint "easyedapro:C0402")
      (description "容值:100nF;精度:±10%;额定电压:16V;材质(温度系数):X7R;")
      (fields
        (field (name "Manufacturer Part") "CC0402KRX7R7BB104")
        (field (name "Manufacturer") "YAGEO(国巨)")
      )
      (libsource (lib "easyedapro") (part "CC0402KRX7R7BB104"))
    )
    (comp (ref "C64")
      (value "33pF")
      (footprint "easyedapro:C0402")
      (description "容值:33pF;精度:±5%;额定电压:50V;材质(温度系数):C0G;")
      (fields (field (name "Manufacturer Part") "C1005C0G1H330J050BA") (field (name "Manufacturer") "TDK"))
      (libsource (lib "easyedapro") (part "C1005C0G1H330J050BA"))
    )
    (comp (ref "C65")
      (value "33pF")
      (footprint "easyedapro:C0402")
      (description "容值:33pF;精度:±5%;额定电压:50V;材质(温度系数):C0G;")
      (fields (field (name "Manufacturer Part") "C1005C0G1H330J050BA") (field (name "Manufacturer") "TDK"))
      (libsource (lib "easyedapro") (part "C1005C0G1H330J050BA"))
    )
    (comp (ref "C66")
      (value "33pF")
      (footprint "easyedapro:C0402")
      (description "容值:33pF;精度:±5%;额定电压:50V;材质(温度系数):C0G;")
      (fields (field (name "Manufacturer Part") "C1005C0G1H330J050BA") (field (name "Manufacturer") "TDK"))
      (libsource (lib "easyedapro") (part "C1005C0G1H330J050BA"))
    )
    (comp (ref "C67")
      (value "33pF")
      (footprint "easyedapro:C0402")
      (description "容值:33pF;精度:±5%;额定电压:50V;材质(温度系数):C0G;")
      (fields (field (name "Manufacturer Part") "C1005C0G1H330J050BA") (field (name "Manufacturer") "TDK"))
      (libsource (lib "easyedapro") (part "C1005C0G1H330J050BA"))
    )
    (comp (ref "C68")
      (value "100nF")
      (footprint "easyedapro:C0402")
      (description "容值:100nF;精度:±10%;额定电压:16V;材质(温度系数):X7R;")
      (fields
        (field (name "Manufacturer Part") "CC0402KRX7R7BB104")
        (field (name "Manufacturer") "YAGEO(国巨)")
      )
      (libsource (lib "easyedapro") (part "CC0402KRX7R7BB104"))
    )
    (comp (ref "C69")
      (value "100nF")
      (footprint "easyedapro:C0402")
      (description "容值:100nF;精度:±10%;额定电压:16V;材质(温度系数):X7R;")
      (fields
        (field (name "Manufacturer Part") "CC0402KRX7R7BB104")
        (field (name "Manufacturer") "YAGEO(国巨)")
      )
      (libsource (lib "easyedapro") (part "CC0402KRX7R7BB104"))
    )
    (comp (ref "CN2")
      (value "HC-PHD-2*4A")
      (footprint "easyedapro:CONN-TH_8P-HC-PHD-2-4A")
      (fields (field (name "Manufacturer") "HCTL(华灿天禄)"))
      (libsource (lib "easyedapro") (part "HC-PHD-2*4A"))
    )
    (comp (ref "CN3")
      (value "HC-PHD-2*4A")
      (footprint "easyedapro:CONN-TH_8P-HC-PHD-2-4A")
      (fields (field (name "Manufacturer") "HCTL(华灿天禄)"))
      (libsource (lib "easyedapro") (part "HC-PHD-2*4A"))
    )
    (comp (ref "L7")
      (value "47nH")
      (footprint "easyedapro:L0402")
      (description "电感值:47nH;精度:±5%;额定电流:250mA;饱和电流(Isat):-;直流电阻(DCR):1.15Ω;")
      (fields (field (name "Manufacturer Part") "LQG15HN47NJ02D") (field (name "Manufacturer") "muRata(村田)"))
      (libsource (lib "easyedapro") (part "LQG15HN47NJ02D"))
    )
    (comp (ref "LED1")
      (value "NET")
      (footprint "easyedapro:LED0603-RD_RED")
      (description "发光颜色:红色;功率:65mW;透镜颜色:无色透明;主波长:615nm~630nm;发光强度:80mcd~220mcd;发光角度:130°;工作温度:-30°C~+85°C;")
      (fields (field (name "Manufacturer Part") "NCD0603R1") (field (name "Manufacturer") "国星光电"))
      (libsource (lib "easyedapro") (part "FC-DA1608HRK-620D"))
    )
    (comp (ref "LED2")
      (value "STATUS")
      (footprint "easyedapro:LED0603-RD_RED")
      (description "发光颜色:红色;功率:65mW;透镜颜色:无色透明;主波长:615nm~630nm;发光强度:80mcd~220mcd;发光角度:130°;工作温度:-30°C~+85°C;")
      (fields (field (name "Manufacturer Part") "NCD0603R1") (field (name "Manufacturer") "国星光电"))
      (libsource (lib "easyedapro") (part "FC-DA1608HRK-620D"))
    )
    (comp (ref "Q1")
      (value "S9013")
      (footprint "easyedapro:SOT-23-3_L2.9-W1.3-P1.90-LS2.4-BR")
      (description "晶体管类型:NPN;集电极电流(Ic):500mA;集射极击穿电压(Vceo):25V;功率(Pd):300mW;")
      (fields (field (name "Manufacturer") "YONGYUTAI(永裕泰)"))
      (libsource (lib "easyedapro") (part "S9013_C2891800"))
    )
    (comp (ref "Q2")
      (value "S9013")
      (footprint "easyedapro:SOT-23-3_L2.9-W1.3-P1.90-LS2.4-BR")
      (description "晶体管类型:NPN;集电极电流(Ic):500mA;集射极击穿电压(Vceo):25V;功率(Pd):300mW;")
      (fields (field (name "Manufacturer") "YONGYUTAI(永裕泰)"))
      (libsource (lib "easyedapro") (part "S9013_C2891800"))
    )
    (comp (ref "R9")
      (value "100kΩ")
      (footprint "easyedapro:R0402")
      (description "电阻类型:厚膜电阻;阻值:100kΩ;精度:±1%;功率:62.5mW;")
      (fields (field (name "Manufacturer Part") "RC0402FR-07100KL") (field (name "Manufacturer") "YAGEO(国巨)"))
      (libsource (lib "easyedapro") (part "RC0402FR-07100KL"))
    )
    (comp (ref "R10")
      (value "1kΩ")
      (footprint "easyedapro:R0402")
      (description "阻值:1kΩ;精度:±1%;功率:62.5mW;温度系数:±100ppm/°C;电阻类型:厚膜电阻;")
      (fields
        (field (name "Manufacturer Part") "0402WGF1001TCE")
        (field (name "Manufacturer") "UNI-ROYAL(厚声)")
      )
      (libsource (lib "easyedapro") (part "0402WGF1001TCE"))
    )
    (comp (ref "R11")
      (value "100kΩ")
      (footprint "easyedapro:R0402")
      (description "电阻类型:厚膜电阻;阻值:100kΩ;精度:±1%;功率:62.5mW;")
      (fields (field (name "Manufacturer Part") "RC0402FR-07100KL") (field (name "Manufacturer") "YAGEO(国巨)"))
      (libsource (lib "easyedapro") (part "RC0402FR-07100KL"))
    )
    (comp (ref "R12")
      (value "1kΩ")
      (footprint "easyedapro:R0402")
      (description "阻值:1kΩ;精度:±1%;功率:62.5mW;温度系数:±100ppm/°C;电阻类型:厚膜电阻;")
      (fields
        (field (name "Manufacturer Part") "0402WGF1001TCE")
        (field (name "Manufacturer") "UNI-ROYAL(厚声)")
      )
      (libsource (lib "easyedapro") (part "0402WGF1001TCE"))
    )
    (comp (ref "R13")
      (value "1kΩ")
      (footprint "easyedapro:R0402")
      (description "阻值:1kΩ;精度:±1%;功率:62.5mW;温度系数:±100ppm/°C;电阻类型:厚膜电阻;")
      (fields
        (field (name "Manufacturer Part") "0402WGF1001TCE")
        (field (name "Manufacturer") "UNI-ROYAL(厚声)")
      )
      (libsource (lib "easyedapro") (part "0402WGF1001TCE"))
    )
    (comp (ref "R14")
      (value "1kΩ")
      (footprint "easyedapro:R0402")
      (description "阻值:1kΩ;精度:±1%;功率:62.5mW;温度系数:±100ppm/°C;电阻类型:厚膜电阻;")
      (fields
        (field (name "Manufacturer Part") "0402WGF1001TCE")
        (field (name "Manufacturer") "UNI-ROYAL(厚声)")
      )
      (libsource (lib "easyedapro") (part "0402WGF1001TCE"))
    )
    (comp (ref "R15")
      (value "0Ω")
      (footprint "easyedapro:R0402")
      (description "阻值:0Ω;精度:±1%;功率:62.5mW;温度系数:±800ppm/°C;电阻类型:厚膜电阻;")
      (fields
        (field (name "Manufacturer Part") "0402WGF0000TCE")
        (field (name "Manufacturer") "UNI-ROYAL(厚声)")
      )
      (libsource (lib "easyedapro") (part "0402WGF0000TCE"))
    )
    (comp (ref "R16")
      (value "0Ω")
      (footprint "easyedapro:R0402")
      (description "阻值:0Ω;精度:±1%;功率:62.5mW;温度系数:±800ppm/°C;电阻类型:厚膜电阻;")
      (fields
        (field (name "Manufacturer Part") "0402WGF0000TCE")
        (field (name "Manufacturer") "UNI-ROYAL(厚声)")
      )
      (libsource (lib "easyedapro") (part "0402WGF0000TCE"))
    )
    (comp (ref "R17")
      (value "0Ω")
      (footprint "easyedapro:R0402")
      (description "电阻类型:厚膜电阻;阻值:0Ω;精度:±5%;功率:62.5mW;最大工作电压:50V;温度系数:-;")
      (fields (field (name "Manufacturer Part") "RC0402JR-070RL") (field (name "Manufacturer") "YAGEO(国巨)"))
      (libsource (lib "easyedapro") (part "RC0402JR-070RL"))
    )
    (comp (ref "R18")
      (value "4.7kΩ")
      (footprint "easyedapro:R0402")
      (description "电阻类型:厚膜电阻;阻值:4.7kΩ;精度:±1%;功率:62.5mW;最大工作电压:50V;温度系数:±100ppm/°C;")
      (fields (field (name "Manufacturer Part") "RC0402FR-074K7L") (field (name "Manufacturer") "YAGEO(国巨)"))
      (libsource (lib "easyedapro") (part "RC0402FR-074K7L"))
    )
    (comp (ref "R29")
      (value "30kΩ")
      (footprint "easyedapro:R0402")
      (description "电阻类型:厚膜电阻;阻值:30kΩ;精度:±1%;功率:62.5mW;最大工作电压:50V;温度系数:±100ppm/°C;")
      (fields (field (name "Manufacturer Part") "RC0402FR-0730KL") (field (name "Manufacturer") "YAGEO(国巨)"))
      (libsource (lib "easyedapro") (part "RC0402FR-0730KL"))
    )
    (comp (ref "R32")
      (value "1kΩ")
      (footprint "easyedapro:R0402")
      (description "阻值:1kΩ;精度:±1%;功率:62.5mW;温度系数:±100ppm/°C;电阻类型:厚膜电阻;")
      (fields
        (field (name "Manufacturer Part") "0402WGF1001TCE")
        (field (name "Manufacturer") "UNI-ROYAL(厚声)")
      )
      (libsource (lib "easyedapro") (part "0402WGF1001TCE"))
    )
    (comp (ref "R33")
      (value "1kΩ")
      (footprint "easyedapro:R0402")
      (description "阻值:1kΩ;精度:±1%;功率:62.5mW;温度系数:±100ppm/°C;电阻类型:厚膜电阻;")
      (fields
        (field (name "Manufacturer Part") "0402WGF1001TCE")
        (field (name "Manufacturer") "UNI-ROYAL(厚声)")
      )
      (libsource (lib "easyedapro") (part "0402WGF1001TCE"))
    )
    (comp (ref "R34")
      (value "1kΩ")
      (footprint "easyedapro:R0402")
      (description "阻值:1kΩ;精度:±1%;功率:62.5mW;温度系数:±100ppm/°C;电阻类型:厚膜电阻;")
      (fields
        (field (name "Manufacturer Part") "0402WGF1001TCE")
        (field (name "Manufacturer") "UNI-ROYAL(厚声)")
      )
      (libsource (lib "easyedapro") (part "0402WGF1001TCE"))
    )
    (comp (ref "R35")
      (value "1kΩ")
      (footprint "easyedapro:R0402")
      (description "阻值:1kΩ;精度:±1%;功率:62.5mW;温度系数:±100ppm/°C;电阻类型:厚膜电阻;")
      (fields
        (field (name "Manufacturer Part") "0402WGF1001TCE")
        (field (name "Manufacturer") "UNI-ROYAL(厚声)")
      )
      (libsource (lib "easyedapro") (part "0402WGF1001TCE"))
    )
    (comp (ref "R36")
      (value "1kΩ")
      (footprint "easyedapro:R0402")
      (description "阻值:1kΩ;精度:±1%;功率:62.5mW;温度系数:±100ppm/°C;电阻类型:厚膜电阻;")
      (fields
        (field (name "Manufacturer Part") "0402WGF1001TCE")
        (field (name "Manufacturer") "UNI-ROYAL(厚声)")
      )
      (libsource (lib "easyedapro") (part "0402WGF1001TCE"))
    )
    (comp (ref "R37")
      (value "1kΩ")
      (footprint "easyedapro:R0402")
      (description "阻值:1kΩ;精度:±1%;功率:62.5mW;温度系数:±100ppm/°C;电阻类型:厚膜电阻;")
      (fields
        (field (name "Manufacturer Part") "0402WGF1001TCE")
        (field (name "Manufacturer") "UNI-ROYAL(厚声)")
      )
      (libsource (lib "easyedapro") (part "0402WGF1001TCE"))
    )
    (comp (ref "RF1")
      (value "KH-IPEX-K501-29")
      (footprint "easyedapro:ANT-SMD_KH-IPEX-K501-29")
      (fields (field (name "Manufacturer") "kinghelm(金航标)"))
      (libsource (lib "easyedapro") (part "KH-IPEX-K501-29"))
    )
    (comp (ref "RF2")
      (value "KH-IPEX-K501-29")
      (footprint "easyedapro:ANT-SMD_KH-IPEX-K501-29")
      (fields (field (name "Manufacturer") "kinghelm(金航标)"))
      (libsource (lib "easyedapro") (part "KH-IPEX-K501-29"))
    )
    (comp (ref "SIM1")
      (value "NANO SIM 7P H1.37")
      (footprint "easyedapro:SIM-SMD_NANO-SIM-7P-H1.37")
      (description "卡连接方式:自弹式;卡类型:NanoSIM卡;连接器类型:卡座;本体最大高度:1.37mm;触头材质:铜合金;触头镀层:金;工作温度范围:-40°C~+70°C;")
      (fields (field (name "Manufacturer") "SHOU HAN(首韩)"))
      (libsource (lib "easyedapro") (part "NANO SIM 7P H1.37"))
    )
    (comp (ref "SW1")
      (value "TS665ZJ")
      (footprint "easyedapro:SW-TH_TS665ZJ")
      (fields (field (name "Manufacturer") "SHOU HAN(首韩)"))
      (libsource (lib "easyedapro") (part "TS665ZJ"))
    )
    (comp (ref "SW2")
      (value "TS665ZJ")
      (footprint "easyedapro:SW-TH_TS665ZJ")
      (fields (field (name "Manufacturer") "SHOU HAN(首韩)"))
      (libsource (lib "easyedapro") (part "TS665ZJ"))
    )
    (comp (ref "U4")
      (value "CH340X")
      (footprint "easyedapro:MSOP-10_L3.0-W3.0-P0.50-LS5.0-BL")
      (fields (field (name "Manufacturer") "WCH(南京沁恒)"))
      (libsource (lib "easyedapro") (part "CH340X"))
    )
    (comp (ref "U6")
      (value "AIR780EG")
      (footprint "easyedapro:LCC-109_L17.7-W15.8-P1.10_EC800M-CN")
      (libsource (lib "easyedapro") (part "AIR780EG"))
    )
    (comp (ref "U7")
      (value "CH340N")
      (footprint "easyedapro:SOP-8_L4.9-W3.9-P1.27-LS6.0-BL")
      (fields (field (name "Manufacturer") "WCH(南京沁恒)"))
      (libsource (lib "easyedapro") (part "CH340N_C2977777"))
    )
    (comp (ref "U8")
      (value "JSGW-eSIM")
      (footprint "easyedapro:TDFN-8_L6.0-W5.0-P1.27-TL-EP")
      (libsource (lib "easyedapro") (part "JSGW-ESIM"))
    )
    (comp (ref "C39")
      (value "1uF")
      (footprint "easyedapro:C0402")
      (description "容值:1uF;精度:±10%;额定电压:10V;材质(温度系数):X5R;")
      (fields
        (field (name "Manufacturer Part") "CC0402KRX5R6BB105")
        (field (name "Manufacturer") "YAGEO(国巨)")
      )
      (libsource (lib "easyedapro") (part "CC0402KRX5R6BB105"))
    )
    (comp (ref "C40")
      (value "1uF")
      (footprint "easyedapro:C0402")
      (description "容值:1uF;精度:±10%;额定电压:10V;材质(温度系数):X5R;")
      (fields
        (field (name "Manufacturer Part") "CC0402KRX5R6BB105")
        (field (name "Manufacturer") "YAGEO(国巨)")
      )
      (libsource (lib "easyedapro") (part "CC0402KRX5R6BB105"))
    )
    (comp (ref "C41")
      (value "1uF")
      (footprint "easyedapro:C0402")
      (description "容值:1uF;精度:±10%;额定电压:10V;材质(温度系数):X5R;")
      (fields
        (field (name "Manufacturer Part") "CC0402KRX5R6BB105")
        (field (name "Manufacturer") "YAGEO(国巨)")
      )
      (libsource (lib "easyedapro") (part "CC0402KRX5R6BB105"))
    )
    (comp (ref "C42")
      (value "3.3uF")
      (footprint "easyedapro:C0402")
      (description "容值:3.3uF;精度:±10%;额定电压:10V;材质(温度系数):X5R;")
      (fields (field (name "Manufacturer Part") "C1005X5R1A335KTJ00E") (field (name "Manufacturer") "TDK"))
      (libsource (lib "easyedapro") (part "C1005X5R1A335KTJ00E"))
    )
    (comp (ref "C43")
      (value "3.3uF")
      (footprint "easyedapro:C0402")
      (description "容值:3.3uF;精度:±10%;额定电压:10V;材质(温度系数):X5R;")
      (fields (field (name "Manufacturer Part") "C1005X5R1A335KTJ00E") (field (name "Manufacturer") "TDK"))
      (libsource (lib "easyedapro") (part "C1005X5R1A335KTJ00E"))
    )
    (comp (ref "C44")
      (value "2.2nF")
      (footprint "easyedapro:C0402")
      (description "容值:2.2nF;精度:±10%;额定电压:50V;材质(温度系数):X7R;")
      (fields
        (field (name "Manufacturer Part") "CC0402KRX7R9BB222")
        (field (name "Manufacturer") "YAGEO(国巨)")
      )
      (libsource (lib "easyedapro") (part "CC0402KRX7R9BB222"))
    )
    (comp (ref "C45")
      (value "2.2nF")
      (footprint "easyedapro:C0402")
      (description "容值:2.2nF;精度:±10%;额定电压:50V;材质(温度系数):X7R;")
      (fields
        (field (name "Manufacturer Part") "CC0402KRX7R9BB222")
        (field (name "Manufacturer") "YAGEO(国巨)")
      )
      (libsource (lib "easyedapro") (part "CC0402KRX7R9BB222"))
    )
    (comp (ref "C46")
      (value "3.3uF")
      (footprint "easyedapro:C0402")
      (description "容值:3.3uF;精度:±10%;额定电压:10V;材质(温度系数):X5R;")
      (fields (field (name "Manufacturer Part") "C1005X5R1A335KTJ00E") (field (name "Manufacturer") "TDK"))
      (libsource (lib "easyedapro") (part "C1005X5R1A335KTJ00E"))
    )
    (comp (ref "C47")
      (value "3.3uF")
      (footprint "easyedapro:C0402")
      (description "容值:3.3uF;精度:±10%;额定电压:10V;材质(温度系数):X5R;")
      (fields (field (name "Manufacturer Part") "C1005X5R1A335KTJ00E") (field (name "Manufacturer") "TDK"))
      (libsource (lib "easyedapro") (part "C1005X5R1A335KTJ00E"))
    )
    (comp (ref "C48")
      (value "2.2nF")
      (footprint "easyedapro:C0402")
      (description "容值:2.2nF;精度:±10%;额定电压:50V;材质(温度系数):X7R;")
      (fields
        (field (name "Manufacturer Part") "CC0402KRX7R9BB222")
        (field (name "Manufacturer") "YAGEO(国巨)")
      )
      (libsource (lib "easyedapro") (part "CC0402KRX7R9BB222"))
    )
    (comp (ref "C49")
      (value "2.2nF")
      (footprint "easyedapro:C0402")
      (description "容值:2.2nF;精度:±10%;额定电压:50V;材质(温度系数):X7R;")
      (fields
        (field (name "Manufacturer Part") "CC0402KRX7R9BB222")
        (field (name "Manufacturer") "YAGEO(国巨)")
      )
      (libsource (lib "easyedapro") (part "CC0402KRX7R9BB222"))
    )
    (comp (ref "C50")
      (value "1uF")
      (footprint "easyedapro:C0402")
      (description "容值:1uF;精度:±10%;额定电压:10V;材质(温度系数):X5R;")
      (fields
        (field (name "Manufacturer Part") "CC0402KRX5R6BB105")
        (field (name "Manufacturer") "YAGEO(国巨)")
      )
      (libsource (lib "easyedapro") (part "CC0402KRX5R6BB105"))
    )
    (comp (ref "C51")
      (value "100nF")
      (footprint "easyedapro:C0402")
      (description "容值:100nF;精度:±10%;额定电压:16V;材质(温度系数):X7R;")
      (fields
        (field (name "Manufacturer Part") "CC0402KRX7R7BB104")
        (field (name "Manufacturer") "YAGEO(国巨)")
      )
      (libsource (lib "easyedapro") (part "CC0402KRX7R7BB104"))
    )
    (comp (ref "C52")
      (value "100nF")
      (footprint "easyedapro:C0402")
      (description "容值:100nF;精度:±10%;额定电压:16V;材质(温度系数):X7R;")
      (fields
        (field (name "Manufacturer Part") "CC0402KRX7R7BB104")
        (field (name "Manufacturer") "YAGEO(国巨)")
      )
      (libsource (lib "easyedapro") (part "CC0402KRX7R7BB104"))
    )
    (comp (ref "C55")
      (value "1uF")
      (footprint "easyedapro:C0402")
      (description "容值:1uF;精度:±10%;额定电压:10V;材质(温度系数):X5R;")
      (fields
        (field (name "Manufacturer Part") "CC0402KRX5R6BB105")
        (field (name "Manufacturer") "YAGEO(国巨)")
      )
      (libsource (lib "easyedapro") (part "CC0402KRX5R6BB105"))
    )
    (comp (ref "C56")
      (value "100nF")
      (footprint "easyedapro:C0402")
      (description "容值:100nF;精度:±10%;额定电压:16V;材质(温度系数):X7R;")
      (fields
        (field (name "Manufacturer Part") "CC0402KRX7R7BB104")
        (field (name "Manufacturer") "YAGEO(国巨)")
      )
      (libsource (lib "easyedapro") (part "CC0402KRX7R7BB104"))
    )
    (comp (ref "C57")
      (value "100nF")
      (footprint "easyedapro:C0402")
      (description "容值:100nF;精度:±10%;额定电压:16V;材质(温度系数):X7R;")
      (fields
        (field (name "Manufacturer Part") "CC0402KRX7R7BB104")
        (field (name "Manufacturer") "YAGEO(国巨)")
      )
      (libsource (lib "easyedapro") (part "CC0402KRX7R7BB104"))
    )
    (comp (ref "C60")
      (value "200pF")
      (footprint "easyedapro:C0402")
      (description "容值:200pF;精度:±5%;额定电压:50V;材质(温度系数):NP0;")
      (fields
        (field (name "Manufacturer Part") "CC0402JRNPO9BN201")
        (field (name "Manufacturer") "YAGEO(国巨)")
      )
      (libsource (lib "easyedapro") (part "CC0402JRNPO9BN201"))
    )
    (comp (ref "C61")
      (value "200pF")
      (footprint "easyedapro:C0402")
      (description "容值:200pF;精度:±5%;额定电压:50V;材质(温度系数):NP0;")
      (fields
        (field (name "Manufacturer Part") "CC0402JRNPO9BN201")
        (field (name "Manufacturer") "YAGEO(国巨)")
      )
      (libsource (lib "easyedapro") (part "CC0402JRNPO9BN201"))
    )
    (comp (ref "C62")
      (value "200pF")
      (footprint "easyedapro:C0402")
      (description "容值:200pF;精度:±5%;额定电压:50V;材质(温度系数):NP0;")
      (fields
        (field (name "Manufacturer Part") "CC0402JRNPO9BN201")
        (field (name "Manufacturer") "YAGEO(国巨)")
      )
      (libsource (lib "easyedapro") (part "CC0402JRNPO9BN201"))
    )
    (comp (ref "C63")
      (value "200pF")
      (footprint "easyedapro:C0402")
      (description "容值:200pF;精度:±5%;额定电压:50V;材质(温度系数):NP0;")
      (fields
        (field (name "Manufacturer Part") "CC0402JRNPO9BN201")
        (field (name "Manufacturer") "YAGEO(国巨)")
      )
      (libsource (lib "easyedapro") (part "CC0402JRNPO9BN201"))
    )
    (comp (ref "L3")
      (value "BLM15PD121SN1D")
      (footprint "easyedapro:L0402")
      (description "标称阻抗@测试频率:120Ω@100MHz;误差:±25%;直流电阻(RDC):90mΩ;")
      (fields (field (name "Manufacturer") "muRata(村田)"))
      (libsource (lib "easyedapro") (part "BLM15PD121SN1D"))
    )
    (comp (ref "L4")
      (value "BLM15PD121SN1D")
      (footprint "easyedapro:L0402")
      (description "标称阻抗@测试频率:120Ω@100MHz;误差:±25%;直流电阻(RDC):90mΩ;")
      (fields (field (name "Manufacturer") "muRata(村田)"))
      (libsource (lib "easyedapro") (part "BLM15PD121SN1D"))
    )
    (comp (ref "L5")
      (value "BLM15PD121SN1D")
      (footprint "easyedapro:L0402")
      (description "标称阻抗@测试频率:120Ω@100MHz;误差:±25%;直流电阻(RDC):90mΩ;")
      (fields (field (name "Manufacturer") "muRata(村田)"))
      (libsource (lib "easyedapro") (part "BLM15PD121SN1D"))
    )
    (comp (ref "L6")
      (value "BLM15PD121SN1D")
      (footprint "easyedapro:L0402")
      (description "标称阻抗@测试频率:120Ω@100MHz;误差:±25%;直流电阻(RDC):90mΩ;")
      (fields (field (name "Manufacturer") "muRata(村田)"))
      (libsource (lib "easyedapro") (part "BLM15PD121SN1D"))
    )
    (comp (ref "R19")
      (value "470Ω")
      (footprint "easyedapro:R0402")
      (description "电阻类型:厚膜电阻;阻值:470Ω;精度:±1%;功率:62.5mW;最大工作电压:50V;温度系数:±100ppm/°C;")
      (fields
        (field (name "Manufacturer Part") "0402WGF4700TCE")
        (field (name "Manufacturer") "UNI-ROYAL(厚声)")
      )
      (libsource (lib "easyedapro") (part "0402WGF4700TCE"))
    )
    (comp (ref "R20")
      (value "470Ω")
      (footprint "easyedapro:R0402")
      (description "电阻类型:厚膜电阻;阻值:470Ω;精度:±1%;功率:62.5mW;最大工作电压:50V;温度系数:±100ppm/°C;")
      (fields
        (field (name "Manufacturer Part") "0402WGF4700TCE")
        (field (name "Manufacturer") "UNI-ROYAL(厚声)")
      )
      (libsource (lib "easyedapro") (part "0402WGF4700TCE"))
    )
    (comp (ref "R21")
      (value "470Ω")
      (footprint "easyedapro:R0402")
      (description "电阻类型:厚膜电阻;阻值:470Ω;精度:±1%;功率:62.5mW;最大工作电压:50V;温度系数:±100ppm/°C;")
      (fields
        (field (name "Manufacturer Part") "0402WGF4700TCE")
        (field (name "Manufacturer") "UNI-ROYAL(厚声)")
      )
      (libsource (lib "easyedapro") (part "0402WGF4700TCE"))
    )
    (comp (ref "R22")
      (value "470Ω")
      (footprint "easyedapro:R0402")
      (description "电阻类型:厚膜电阻;阻值:470Ω;精度:±1%;功率:62.5mW;最大工作电压:50V;温度系数:±100ppm/°C;")
      (fields
        (field (name "Manufacturer Part") "0402WGF4700TCE")
        (field (name "Manufacturer") "UNI-ROYAL(厚声)")
      )
      (libsource (lib "easyedapro") (part "0402WGF4700TCE"))
    )
    (comp (ref "R23")
      (value "1kΩ")
      (footprint "easyedapro:R0402")
      (description "阻值:1kΩ;精度:±1%;功率:62.5mW;温度系数:±100ppm/°C;电阻类型:厚膜电阻;")
      (fields
        (field (name "Manufacturer Part") "0402WGF1001TCE")
        (field (name "Manufacturer") "UNI-ROYAL(厚声)")
      )
      (libsource (lib "easyedapro") (part "0402WGF1001TCE"))
    )
    (comp (ref "R24")
      (value "30kΩ")
      (footprint "easyedapro:R0402")
      (description "电阻类型:厚膜电阻;阻值:30kΩ;精度:±1%;功率:62.5mW;最大工作电压:50V;温度系数:±100ppm/°C;")
      (fields (field (name "Manufacturer Part") "RC0402FR-0730KL") (field (name "Manufacturer") "YAGEO(国巨)"))
      (libsource (lib "easyedapro") (part "RC0402FR-0730KL"))
    )
    (comp (ref "R25")
      (value "30kΩ")
      (footprint "easyedapro:R0402")
      (description "电阻类型:厚膜电阻;阻值:30kΩ;精度:±1%;功率:62.5mW;最大工作电压:50V;温度系数:±100ppm/°C;")
      (fields (field (name "Manufacturer Part") "RC0402FR-0730KL") (field (name "Manufacturer") "YAGEO(国巨)"))
      (libsource (lib "easyedapro") (part "RC0402FR-0730KL"))
    )
    (comp (ref "R26")
      (value "1kΩ")
      (footprint "easyedapro:R0402")
      (description "阻值:1kΩ;精度:±1%;功率:62.5mW;温度系数:±100ppm/°C;电阻类型:厚膜电阻;")
      (fields
        (field (name "Manufacturer Part") "0402WGF1001TCE")
        (field (name "Manufacturer") "UNI-ROYAL(厚声)")
      )
      (libsource (lib "easyedapro") (part "0402WGF1001TCE"))
    )
    (comp (ref "R27")
      (value "30kΩ")
      (footprint "easyedapro:R0402")
      (description "电阻类型:厚膜电阻;阻值:30kΩ;精度:±1%;功率:62.5mW;最大工作电压:50V;温度系数:±100ppm/°C;")
      (fields (field (name "Manufacturer Part") "RC0402FR-0730KL") (field (name "Manufacturer") "YAGEO(国巨)"))
      (libsource (lib "easyedapro") (part "RC0402FR-0730KL"))
    )
    (comp (ref "R28")
      (value "30kΩ")
      (footprint "easyedapro:R0402")
      (description "电阻类型:厚膜电阻;阻值:30kΩ;精度:±1%;功率:62.5mW;最大工作电压:50V;温度系数:±100ppm/°C;")
      (fields (field (name "Manufacturer Part") "RC0402FR-0730KL") (field (name "Manufacturer") "YAGEO(国巨)"))
      (libsource (lib "easyedapro") (part "RC0402FR-0730KL"))
    )
    (comp (ref "SPK1")
      (value "GSPK2307P-8R1W")
      (footprint "easyedapro:SPK-TH_BD23.0-P10.00-D0.8-L-RD")
      (fields (field (name "Manufacturer") "INGHAi(赢海)"))
      (libsource (lib "easyedapro") (part "GSPK2307P-8R1W"))
    )
    (comp (ref "SPK2")
      (value "GSPK2307P-8R1W")
      (footprint "easyedapro:SPK-TH_BD23.0-P10.00-D0.8-L-RD")
      (fields (field (name "Manufacturer") "INGHAi(赢海)"))
      (libsource (lib "easyedapro") (part "GSPK2307P-8R1W"))
    )
    (comp (ref "U9")
      (value "ES7149")
      (footprint "easyedapro:QFN-12_L2.5-W2.5-P0.50-BL-EP")
      (fields (field (name "Manufacturer") "Everest-semi(顺芯)"))
      (libsource (lib "easyedapro") (part "ES7149"))
    )
    (comp (ref "U10")
      (value "EG8305")
      (footprint "easyedapro:SOIC-8_L5.0-W4.0-P1.27-LS6.0-BL")
      (description "功放类型:D类功放;扬声器通道数:单声道;输出功率:3Wx1@4Ω;")
      (fields (field (name "Manufacturer") "EG(屹晶微)"))
      (libsource (lib "easyedapro") (part "EG8305_C266226"))
    )
    (comp (ref "U11")
      (value "EG8305")
      (footprint "easyedapro:SOIC-8_L5.0-W4.0-P1.27-LS6.0-BL")
      (description "功放类型:D类功放;扬声器通道数:单声道;输出功率:3Wx1@4Ω;")
      (fields (field (name "Manufacturer") "EG(屹晶微)"))
      (libsource (lib "easyedapro") (part "EG8305_C266226"))
    )
    (comp (ref "CN1")
      (value "HC-ZH1.5-4A")
      (footprint "easyedapro:CONN-TH_4P-P1.50_HCTL_HC-ZH1.5-4A")
      (fields (field (name "Manufacturer") "HCTL(华灿天禄)"))
      (libsource (lib "easyedapro") (part "HC-ZH1.5-4A"))
    )
    (comp (ref "R30")
      (value "5.1kΩ")
      (footprint "easyedapro:R0402")
      (description "阻值:5.1kΩ;精度:±1%;功率:62.5mW;温度系数:±100ppm/°C;电阻类型:厚膜电阻;")
      (fields
        (field (name "Manufacturer Part") "0402WGF5101TCE")
        (field (name "Manufacturer") "UNI-ROYAL(厚声)")
      )
      (libsource (lib "easyedapro") (part "0402WGF5101TCE"))
    )
    (comp (ref "R31")
      (value "5.1kΩ")
      (footprint "easyedapro:R0402")
      (description "阻值:5.1kΩ;精度:±1%;功率:62.5mW;温度系数:±100ppm/°C;电阻类型:厚膜电阻;")
      (fields
        (field (name "Manufacturer Part") "0402WGF5101TCE")
        (field (name "Manufacturer") "UNI-ROYAL(厚声)")
      )
      (libsource (lib "easyedapro") (part "0402WGF5101TCE"))
    )
    (comp (ref "U12")
      (value "AHT20")
      (footprint "easyedapro:SENSOR-SMD_L3.0-W3.0-P1.00-BR")
      (fields (field (name "Manufacturer") "广州奥松"))
      (libsource (lib "easyedapro") (part "AHT20_C2757850"))
    )
  )
  (nets
    (net (code "1") (name "3V3") (class "Default")
      (node (ref "C15") (pin "2") (pinfunction "2_2") (pintype "unspecified"))
      (node (ref "C16") (pin "2") (pinfunction "2_2") (pintype "input"))
      (node (ref "C21") (pin "1") (pinfunction "1_1") (pintype "unspecified"))
      (node (ref "C22") (pin "1") (pinfunction "1_1") (pintype "input"))
      (node (ref "C24") (pin "1") (pinfunction "1_1") (pintype "unspecified"))
      (node (ref "C35") (pin "1") (pinfunction "1_1") (pintype "input"))
      (node (ref "C36") (pin "1") (pinfunction "1_1") (pintype "unspecified"))
      (node (ref "C41") (pin "2") (pinfunction "2_2") (pintype "unspecified"))
      (node (ref "CN1") (pin "2") (pinfunction "2_2") (pintype "unspecified"))
      (node (ref "CN2") (pin "1") (pinfunction "1_1") (pintype "unspecified"))
      (node (ref "CN3") (pin "1") (pinfunction "1_1") (pintype "unspecified"))
      (node (ref "L1") (pin "2") (pinfunction "2_2") (pintype "input"))
      (node (ref "LED1") (pin "2") (pinfunction "A_2") (pintype "input"))
      (node (ref "LED2") (pin "2") (pinfunction "A_2") (pintype "input"))
      (node (ref "R12") (pin "1") (pinfunction "1_1") (pintype "input"))
      (node (ref "R23") (pin "2") (pinfunction "2_2") (pintype "input"))
      (node (ref "R26") (pin "2") (pinfunction "2_2") (pintype "input"))
      (node (ref "R29") (pin "1") (pinfunction "1_1") (pintype "input"))
      (node (ref "R30") (pin "1") (pinfunction "1_1") (pintype "input"))
      (node (ref "R31") (pin "2") (pinfunction "2_2") (pintype "input"))
      (node (ref "R4") (pin "1") (pinfunction "1_1") (pintype "input"))
      (node (ref "SW2") (pin "2") (pinfunction "2_2") (pintype "input"))
      (node (ref "U10") (pin "6") (pinfunction "VDD_6") (pintype "unspecified"))
      (node (ref "U11") (pin "6") (pinfunction "VDD_6") (pintype "unspecified"))
      (node (ref "U12") (pin "2") (pinfunction "VDD_2") (pintype "unspecified"))
      (node (ref "U4") (pin "10") (pinfunction "V3_10") (pintype "unspecified"))
      (node (ref "U4") (pin "7") (pinfunction "VCC_7") (pintype "unspecified"))
      (node (ref "U7") (pin "5") (pinfunction "VCC_5") (pintype "unspecified"))
      (node (ref "U7") (pin "8") (pinfunction "V3_8") (pintype "unspecified"))
      (node (ref "U9") (pin "9") (pinfunction "VDD_9") (pintype "input"))
    )
    (net (code "2") (name "ADC0") (class "Default")
      (node (ref "CN3") (pin "6") (pinfunction "6_6") (pintype "unspecified"))
      (node (ref "U6") (pin "9") (pinfunction "ADC0_9") (pintype "unspecified"))
    )
    (net (code "3") (name "ADC1") (class "Default")
      (node (ref "CN3") (pin "7") (pinfunction "7_7") (pintype "unspecified"))
      (node (ref "U6") (pin "96") (pinfunction "ADC1_96") (pintype "unspecified"))
    )
    (net (code "4") (name "D-RXD") (class "Default")
      (node (ref "R35") (pin "1") (pinfunction "1_1") (pintype "input"))
      (node (ref "U6") (pin "38") (pinfunction "DBG_RXD_38") (pintype "unspecified"))
    )
    (net (code "5") (name "D-TXD") (class "Default")
      (node (ref "R34") (pin "1") (pinfunction "1_1") (pintype "input"))
      (node (ref "U6") (pin "39") (pinfunction "DBG_TXD_39") (pintype "unspecified"))
    )
    (net (code "6") (name "DM-UP") (class "Default")
      (node (ref "U1") (pin "10") (pinfunction "DMU_10") (pintype "unspecified"))
      (node (ref "USB1") (pin "5") (pinfunction "DN2_5") (pintype "unspecified"))
      (node (ref "USB1") (pin "7") (pinfunction "DN1_7") (pintype "unspecified"))
    )
    (net (code "7") (name "DM1") (class "Default")
      (node (ref "U1") (pin "7") (pinfunction "DM1_7") (pintype "unspecified"))
      (node (ref "U6") (pin "60") (pinfunction "USB_DN_60") (pintype "unspecified"))
    )
    (net (code "8") (name "DM2") (class "Default")
      (node (ref "U1") (pin "5") (pinfunction "DM2_5") (pintype "unspecified"))
      (node (ref "U4") (pin "2") (pinfunction "UD-_2") (pintype "unspecified"))
    )
    (net (code "9") (name "DM3") (class "Default")
      (node (ref "U1") (pin "3") (pinfunction "DM3_3") (pintype "unspecified"))
      (node (ref "U7") (pin "2") (pinfunction "UD-_2") (pintype "unspecified"))
    )
    (net (code "10") (name "DM4") (class "Default")
      (node (ref "U1") (pin "1") (pinfunction "DM4_1") (pintype "unspecified"))
      (node (ref "U2") (pin "10") (pinfunction "DMU_10") (pintype "unspecified"))
    )
    (net (code "11") (name "DP-UP") (class "Default")
      (node (ref "U1") (pin "11") (pinfunction "DPU_11") (pintype "unspecified"))
      (node (ref "USB1") (pin "6") (pinfunction "DP1_6") (pintype "unspecified"))
      (node (ref "USB1") (pin "8") (pinfunction "DP2_8") (pintype "unspecified"))
    )
    (net (code "12") (name "DP1") (class "Default")
      (node (ref "U1") (pin "8") (pinfunction "DP1_8") (pintype "unspecified"))
      (node (ref "U6") (pin "59") (pinfunction "USB_DP_59") (pintype "unspecified"))
    )
    (net (code "13") (name "DP2") (class "Default")
      (node (ref "U1") (pin "6") (pinfunction "DP2_6") (pintype "unspecified"))
      (node (ref "U4") (pin "1") (pinfunction "UD+_1") (pintype "unspecified"))
    )
    (net (code "14") (name "DP3") (class "Default")
      (node (ref "U1") (pin "4") (pinfunction "DP3_4") (pintype "unspecified"))
      (node (ref "U7") (pin "1") (pinfunction "UD+_1") (pintype "unspecified"))
    )
    (net (code "15") (name "DP4") (class "Default")
      (node (ref "U1") (pin "2") (pinfunction "DP4_2") (pintype "unspecified"))
      (node (ref "U2") (pin "11") (pinfunction "DPU_11") (pintype "unspecified"))
    )
    (net (code "16") (name "GND") (class "Default")
      (node (ref "C1") (pin "1") (pinfunction "1_1") (pintype "input"))
      (node (ref "C10") (pin "2") (pinfunction "2_2") (pintype "input"))
      (node (ref "C11") (pin "1") (pinfunction "1_1") (pintype "input"))
      (node (ref "C12") (pin "1") (pinfunction "1_1") (pintype "unspecified"))
      (node (ref "C13") (pin "1") (pinfunction "1_1") (pintype "input"))
      (node (ref "C14") (pin "1") (pinfunction "1_1") (pintype "unspecified"))
      (node (ref "C15") (pin "1") (pinfunction "1_1") (pintype "unspecified"))
      (node (ref "C16") (pin "1") (pinfunction "1_1") (pintype "input"))
      (node (ref "C17") (pin "1") (pinfunction "1_1") (pintype "input"))
      (node (ref "C19") (pin "2") (pinfunction "2_2") (pintype "input"))
      (node (ref "C2") (pin "2") (pinfunction "2_2") (pintype "input"))
      (node (ref "C20") (pin "2") (pinfunction "2_2") (pintype "input"))
      (node (ref "C21") (pin "2") (pinfunction "2_2") (pintype "unspecified"))
      (node (ref "C22") (pin "2") (pinfunction "2_2") (pintype "input"))
      (node (ref "C23") (pin "1") (pinfunction "1_1") (pintype "unspecified"))
      (node (ref "C25") (pin "1") (pinfunction "1_1") (pintype "input"))
      (node (ref "C26") (pin "1") (pinfunction "1_1") (pintype "unspecified"))
      (node (ref "C27") (pin "1") (pinfunction "1_1") (pintype "input"))
      (node (ref "C28") (pin "1") (pinfunction "1_1") (pintype "input"))
      (node (ref "C29") (pin "1") (pinfunction "1_1") (pintype "unspecified"))
      (node (ref "C3") (pin "1") (pinfunction "1_1") (pintype "input"))
      (node (ref "C30") (pin "1") (pinfunction "1_1") (pintype "input"))
      (node (ref "C31") (pin "1") (pinfunction "1_1") (pintype "input"))
      (node (ref "C32") (pin "1") (pinfunction "1_1") (pintype "input"))
      (node (ref "C33") (pin "1") (pinfunction "1_1") (pintype "input"))
      (node (ref "C34") (pin "1") (pinfunction "1_1") (pintype "input"))
      (node (ref "C35") (pin "2") (pinfunction "2_2") (pintype "input"))
      (node (ref "C36") (pin "2") (pinfunction "2_2") (pintype "unspecified"))
      (node (ref "C37") (pin "1") (pinfunction "1_1") (pintype "input"))
      (node (ref "C38") (pin "1") (pinfunction "1_1") (pintype "unspecified"))
      (node (ref "C39") (pin "1") (pinfunction "1_1") (pintype "unspecified"))
      (node (ref "C4") (pin "1") (pinfunction "1_1") (pintype "unspecified"))
      (node (ref "C40") (pin "1") (pinfunction "1_1") (pintype "unspecified"))
      (node (ref "C41") (pin "1") (pinfunction "1_1") (pintype "unspecified"))
      (node (ref "C44") (pin "2") (pinfunction "2_2") (pintype "input"))
      (node (ref "C45") (pin "1") (pinfunction "1_1") (pintype "input"))
      (node (ref "C48") (pin "2") (pinfunction "2_2") (pintype "input"))
      (node (ref "C49") (pin "1") (pinfunction "1_1") (pintype "input"))
      (node (ref "C5") (pin "1") (pinfunction "1_1") (pintype "input"))
      (node (ref "C50") (pin "1") (pinfunction "1_1") (pintype "unspecified"))
      (node (ref "C55") (pin "1") (pinfunction "1_1") (pintype "unspecified"))
      (node (ref "C6") (pin "1") (pinfunction "1_1") (pintype "unspecified"))
      (node (ref "C60") (pin "1") (pinfunction "1_1") (pintype "unspecified"))
      (node (ref "C61") (pin "2") (pinfunction "2_2") (pintype "unspecified"))
      (node (ref "C62") (pin "2") (pinfunction "2_2") (pintype "unspecified"))
      (node (ref "C63") (pin "1") (pinfunction "1_1") (pintype "unspecified"))
      (node (ref "C64") (pin "2") (pinfunction "2_2") (pintype "input"))
      (node (ref "C65") (pin "2") (pinfunction "2_2") (pintype "input"))
      (node (ref "C66") (pin "2") (pinfunction "2_2") (pintype "input"))
      (node (ref "C67") (pin "2") (pinfunction "2_2") (pintype "input"))
      (node (ref "C68") (pin "2") (pinfunction "2_2") (pintype "unspecified"))
      (node (ref "C69") (pin "1") (pinfunction "1_1") (pintype "unspecified"))
      (node (ref "C7") (pin "2") (pinfunction "2_2") (pintype "input"))
      (node (ref "C8") (pin "2") (pinfunction "2_2") (pintype "input"))
      (node (ref "C9") (pin "1") (pinfunction "1_1") (pintype "input"))
      (node (ref "CN1") (pin "1") (pinfunction "1_1") (pintype "unspecified"))
      (node (ref "CN2") (pin "8") (pinfunction "8_8") (pintype "unspecified"))
      (node (ref "CN3") (pin "5") (pinfunction "5_5") (pintype "unspecified"))
      (node (ref "CN3") (pin "8") (pinfunction "8_8") (pintype "unspecified"))
      (node (ref "Q1") (pin "2") (pinfunction "E_2") (pintype "unspecified"))
      (node (ref "Q2") (pin "2") (pinfunction "E_2") (pintype "unspecified"))
      (node (ref "R1") (pin "2") (pinfunction "2_2") (pintype "input"))
      (node (ref "R14") (pin "1") (pinfunction "1_1") (pintype "input"))
      (node (ref "R2") (pin "2") (pinfunction "2_2") (pintype "input"))
      (node (ref "R5") (pin "2") (pinfunction "2_2") (pintype "input"))
      (node (ref "R8") (pin "2") (pinfunction "2_2") (pintype "input"))
      (node (ref "RF1") (pin "1") (pinfunction "GND_1") (pintype "unspecified"))
      (node (ref "RF1") (pin "2") (pinfunction "GND_2") (pintype "unspecified"))
      (node (ref "RF1") (pin "3") (pinfunction "GND_3") (pintype "unspecified"))
      (node (ref "RF2") (pin "1") (pinfunction "GND_1") (pintype "unspecified"))
      (node (ref "RF2") (pin "2") (pinfunction "GND_2") (pintype "unspecified"))
      (node (ref "RF2") (pin "3") (pinfunction "GND_3") (pintype "unspecified"))
      (node (ref "SIM1") (pin "10") (pinfunction "GND_10") (pintype "unspecified"))
      (node (ref "SIM1") (pin "11") (pinfunction "GND_11") (pintype "unspecified"))
      (node (ref "SIM1") (pin "12") (pinfunction "GND_12") (pintype "unspecified"))
      (node (ref "SIM1") (pin "5") (pinfunction "GND_5") (pintype "unspecified"))
      (node (ref "SIM1") (pin "9") (pinfunction "GND_9") (pintype "unspecified"))
      (node (ref "SW1") (pin "2") (pinfunction "2_2") (pintype "input"))
      (node (ref "SW1") (pin "3") (pinfunction "3_3") (pintype "input"))
      (node (ref "SW1") (pin "4") (pinfunction "4_4") (pintype "input"))
      (node (ref "SW2") (pin "3") (pinfunction "3_3") (pintype "input"))
      (node (ref "SW2") (pin "4") (pinfunction "4_4") (pintype "input"))
      (node (ref "U1") (pin "14") (pinfunction "GND_14") (pintype "unspecified"))
      (node (ref "U10") (pin "7") (pinfunction "GND_7") (pintype "unspecified"))
      (node (ref "U11") (pin "7") (pinfunction "GND_7") (pintype "unspecified"))
      (node (ref "U12") (pin "5") (pinfunction "GND_5") (pintype "unspecified"))
      (node (ref "U2") (pin "14") (pinfunction "GND_14") (pintype "unspecified"))
      (node (ref "U3") (pin "2") (pinfunction "GND_2") (pintype "input"))
      (node (ref "U4") (pin "3") (pinfunction "GND_3") (pintype "unspecified"))
      (node (ref "U5") (pin "1") (pinfunction "GND_1") (pintype "input"))
      (node (ref "U6") (pin "1") (pinfunction "GND_1") (pintype "unspecified"))
      (node (ref "U6") (pin "10") (pinfunction "GND_10") (pintype "unspecified"))
      (node (ref "U6") (pin "100") (pinfunction "IO_1833_SEL_100") (pintype "unspecified"))
      (node (ref "U6") (pin "27") (pinfunction "GND_27") (pintype "unspecified"))
      (node (ref "U6") (pin "34") (pinfunction "GND_34") (pintype "unspecified"))
      (node (ref "U6") (pin "36") (pinfunction "GND_36") (pintype "unspecified"))
      (node (ref "U6") (pin "37") (pinfunction "GND_37") (pintype "unspecified"))
      (node (ref "U6") (pin "40") (pinfunction "GND_40") (pintype "unspecified"))
      (node (ref "U6") (pin "41") (pinfunction "GND_41") (pintype "unspecified"))
      (node (ref "U6") (pin "45") (pinfunction "GND_45") (pintype "unspecified"))
      (node (ref "U6") (pin "46") (pinfunction "GND_46") (pintype "unspecified"))
      (node (ref "U6") (pin "47") (pinfunction "GND_47") (pintype "unspecified"))
      (node (ref "U6") (pin "48") (pinfunction "GND_48") (pintype "unspecified"))
      (node (ref "U6") (pin "7") (pinfunction "PWRKEY_7") (pintype "unspecified"))
      (node (ref "U6") (pin "70") (pinfunction "GND_70") (pintype "unspecified"))
      (node (ref "U6") (pin "71") (pinfunction "GND_71") (pintype "unspecified"))
      (node (ref "U6") (pin "72") (pinfunction "GND_72") (pintype "unspecified"))
      (node (ref "U6") (pin "73") (pinfunction "GND_73") (pintype "unspecified"))
      (node (ref "U6") (pin "88") (pinfunction "GND_88") (pintype "unspecified"))
      (node (ref "U6") (pin "89") (pinfunction "GND_89") (pintype "unspecified"))
      (node (ref "U6") (pin "90") (pinfunction "GND_90") (pintype "unspecified"))
      (node (ref "U6") (pin "91") (pinfunction "GND_91") (pintype "unspecified"))
      (node (ref "U6") (pin "92") (pinfunction "GND_92") (pintype "unspecified"))
      (node (ref "U6") (pin "93") (pinfunction "GND_93") (pintype "unspecified"))
      (node (ref "U6") (pin "94") (pinfunction "GND_94") (pintype "unspecified"))
      (node (ref "U6") (pin "95") (pinfunction "GND_95") (pintype "unspecified"))
      (node (ref "U7") (pin "3") (pinfunction "GND_3") (pintype "unspecified"))
      (node (ref "U8") (pin "1") (pinfunction "GND_1") (pintype "unspecified"))
      (node (ref "U8") (pin "9") (pinfunction "EP_9") (pintype "unspecified"))
      (node (ref "U9") (pin "13") (pinfunction "EP_13") (pintype "input"))
      (node (ref "U9") (pin "8") (pinfunction "GND_8") (pintype "input"))
      (node (ref "USB1") (pin "1") (pinfunction "GND_1") (pintype "unspecified"))
      (node (ref "USB1") (pin "12") (pinfunction "GND_12") (pintype "unspecified"))
      (node (ref "USB1") (pin "13") (pinfunction "SHELL_13") (pintype "unspecified"))
      (node (ref "USB1") (pin "14") (pinfunction "SHELL_14") (pintype "unspecified"))
      (node (ref "USB2") (pin "10") (pinfunction "SHELL_10") (pintype "unspecified"))
      (node (ref "USB2") (pin "11") (pinfunction "SHELL_11") (pintype "unspecified"))
      (node (ref "USB2") (pin "12") (pinfunction "SHELL_12") (pintype "unspecified"))
      (node (ref "USB2") (pin "4") (pinfunction "GND_4") (pintype "unspecified"))
      (node (ref "USB2") (pin "8") (pinfunction "GND_8") (pintype "unspecified"))
      (node (ref "USB2") (pin "9") (pinfunction "SHELL_9") (pintype "unspecified"))
      (node (ref "USB3") (pin "10") (pinfunction "SHELL_10") (pintype "unspecified"))
      (node (ref "USB3") (pin "11") (pinfunction "SHELL_11") (pintype "unspecified"))
      (node (ref "USB3") (pin "12") (pinfunction "SHELL_12") (pintype "unspecified"))
      (node (ref "USB3") (pin "4") (pinfunction "GND_4") (pintype "unspecified"))
      (node (ref "USB3") (pin "8") (pinfunction "GND_8") (pintype "unspecified"))
      (node (ref "USB3") (pin "9") (pinfunction "SHELL_9") (pintype "unspecified"))
      (node (ref "X1") (pin "2") (pinfunction "GND_2") (pintype "unspecified"))
      (node (ref "X1") (pin "4") (pinfunction "GND_4") (pintype "unspecified"))
      (node (ref "X2") (pin "2") (pinfunction "GND_2") (pintype "unspecified"))
      (node (ref "X2") (pin "4") (pinfunction "GND_4") (pintype "unspecified"))
    )
    (net (code "17") (name "GPIO20") (class "Default")
      (node (ref "CN3") (pin "4") (pinfunction "4_4") (pintype "unspecified"))
      (node (ref "U6") (pin "102") (pinfunction "AGPIOWU0_102") (pintype "unspecified"))
    )
    (net (code "18") (name "GPIO21") (class "Default")
      (node (ref "CN3") (pin "2") (pinfunction "2_2") (pintype "unspecified"))
      (node (ref "U6") (pin "107") (pinfunction "AGPIOWU1_107") (pintype "unspecified"))
    )
    (net (code "19") (name "GPIO25") (class "Default")
      (node (ref "CN3") (pin "3") (pinfunction "3_3") (pintype "unspecified"))
      (node (ref "U6") (pin "106") (pinfunction "AGPIO5_106") (pintype "unspecified"))
    )
    (net (code "20") (name "HUB_DM1") (class "Default")
      (node (ref "U2") (pin "7") (pinfunction "DM1_7") (pintype "unspecified"))
      (node (ref "USB2") (pin "2") (pinfunction "D-_2") (pintype "unspecified"))
    )
    (net (code "21") (name "HUB_DM2") (class "Default")
      (node (ref "U2") (pin "5") (pinfunction "DM2_5") (pintype "unspecified"))
      (node (ref "USB2") (pin "6") (pinfunction "D-_6") (pintype "unspecified"))
    )
    (net (code "22") (name "HUB_DM3") (class "Default")
      (node (ref "U2") (pin "3") (pinfunction "DM3_3") (pintype "unspecified"))
      (node (ref "USB3") (pin "2") (pinfunction "D-_2") (pintype "unspecified"))
    )
    (net (code "23") (name "HUB_DM4") (class "Default")
      (node (ref "U2") (pin "1") (pinfunction "DM4_1") (pintype "unspecified"))
      (node (ref "USB3") (pin "6") (pinfunction "D-_6") (pintype "unspecified"))
    )
    (net (code "24") (name "HUB_DP1") (class "Default")
      (node (ref "U2") (pin "8") (pinfunction "DP1_8") (pintype "unspecified"))
      (node (ref "USB2") (pin "3") (pinfunction "D+_3") (pintype "unspecified"))
    )
    (net (code "25") (name "HUB_DP2") (class "Default")
      (node (ref "U2") (pin "6") (pinfunction "DP2_6") (pintype "unspecified"))
      (node (ref "USB2") (pin "7") (pinfunction "D+_7") (pintype "unspecified"))
    )
    (net (code "26") (name "HUB_DP3") (class "Default")
      (node (ref "U2") (pin "4") (pinfunction "DP3_4") (pintype "unspecified"))
      (node (ref "USB3") (pin "3") (pinfunction "D+_3") (pintype "unspecified"))
    )
    (net (code "27") (name "HUB_DP4") (class "Default")
      (node (ref "U2") (pin "2") (pinfunction "DP4_2") (pintype "unspecified"))
      (node (ref "USB3") (pin "7") (pinfunction "D+_7") (pintype "unspecified"))
    )
    (net (code "28") (name "I2C-SCL") (class "Default")
      (node (ref "CN1") (pin "3") (pinfunction "3_3") (pintype "unspecified"))
      (node (ref "R30") (pin "2") (pinfunction "2_2") (pintype "input"))
      (node (ref "U12") (pin "3") (pinfunction "SCL_3") (pintype "unspecified"))
      (node (ref "U6") (pin "67") (pinfunction "I2C_SCL_67") (pintype "unspecified"))
    )
    (net (code "29") (name "I2C-SDA") (class "Default")
      (node (ref "CN1") (pin "4") (pinfunction "4_4") (pintype "unspecified"))
      (node (ref "R31") (pin "1") (pinfunction "1_1") (pintype "input"))
      (node (ref "U12") (pin "4") (pinfunction "SDA_4") (pintype "unspecified"))
      (node (ref "U6") (pin "66") (pinfunction "I2C_SDA_66") (pintype "unspecified"))
    )
    (net (code "30") (name "I2S-BCK") (class "Default")
      (node (ref "U6") (pin "30") (pinfunction "I2S_BCK_30") (pintype "unspecified"))
      (node (ref "U9") (pin "1") (pinfunction "SCLK_1") (pintype "input"))
    )
    (net (code "31") (name "I2S-DIN") (class "Default")
      (node (ref "U6") (pin "32") (pinfunction "I2S_DIN_32") (pintype "unspecified"))
    )
    (net (code "32") (name "I2S-DOUT") (class "Default")
      (node (ref "U6") (pin "33") (pinfunction "I2S_DOUT_33") (pintype "unspecified"))
      (node (ref "U9") (pin "12") (pinfunction "SDATA_12") (pintype "input"))
    )
    (net (code "33") (name "I2S-LRCK") (class "Default")
      (node (ref "U6") (pin "31") (pinfunction "I2S_LRCK_31") (pintype "unspecified"))
      (node (ref "U9") (pin "2") (pinfunction "LRCK_2") (pintype "input"))
    )
    (net (code "34") (name "I2S-MCLK") (class "Default")
      (node (ref "U6") (pin "26") (pinfunction "I2S_MCLK_26") (pintype "unspecified"))
      (node (ref "U9") (pin "3") (pinfunction "CLKIN_3") (pintype "input"))
    )
    (net (code "35") (name "L-SPKN") (class "Default")
      (node (ref "C49") (pin "2") (pinfunction "2_2") (pintype "input"))
      (node (ref "C52") (pin "1") (pinfunction "1_1") (pintype "unspecified"))
      (node (ref "R22") (pin "2") (pinfunction "2_2") (pintype "input"))
    )
    (net (code "36") (name "L-SPKP") (class "Default")
      (node (ref "C48") (pin "1") (pinfunction "1_1") (pintype "input"))
      (node (ref "C51") (pin "1") (pinfunction "1_1") (pintype "unspecified"))
      (node (ref "R21") (pin "2") (pinfunction "2_2") (pintype "input"))
    )
    (net (code "37") (name "LCD-CLK") (class "Default")
      (node (ref "CN2") (pin "6") (pinfunction "6_6") (pintype "unspecified"))
      (node (ref "U6") (pin "53") (pinfunction "LCD_CLK_53") (pintype "unspecified"))
    )
    (net (code "38") (name "LCD-CS") (class "Default")
      (node (ref "CN2") (pin "5") (pinfunction "5_5") (pintype "unspecified"))
      (node (ref "U6") (pin "52") (pinfunction "LCD_CS_52") (pintype "unspecified"))
    )
    (net (code "39") (name "LCD-DOUT") (class "Default")
      (node (ref "CN2") (pin "3") (pinfunction "3_3") (pintype "unspecified"))
      (node (ref "U6") (pin "50") (pinfunction "LCD_DOUT_50") (pintype "unspecified"))
    )
    (net (code "40") (name "LCD-RS") (class "Default")
      (node (ref "CN2") (pin "4") (pinfunction "4_4") (pintype "unspecified"))
      (node (ref "U6") (pin "51") (pinfunction "LCD_RS_51") (pintype "unspecified"))
    )
    (net (code "41") (name "LCD-RST") (class "Default")
      (node (ref "CN2") (pin "2") (pinfunction "2_2") (pintype "unspecified"))
      (node (ref "U6") (pin "49") (pinfunction "LCD_RST_49") (pintype "unspecified"))
    )
    (net (code "42") (name "LCD-TE") (class "Default")
      (node (ref "CN2") (pin "7") (pinfunction "7_7") (pintype "unspecified"))
      (node (ref "U6") (pin "78") (pinfunction "LCD_TE_78") (pintype "unspecified"))
    )
    (net (code "43") (name "M-CTS") (class "Default")
      (node (ref "R36") (pin "2") (pinfunction "2_2") (pintype "input"))
      (node (ref "U6") (pin "22") (pinfunction "MAIN_CTS_22") (pintype "unspecified"))
    )
    (net (code "44") (name "M-DCD") (class "Default")
      (node (ref "U6") (pin "21") (pinfunction "MAIN_DCD_21") (pintype "unspecified"))
    )
    (net (code "45") (name "M-DTR") (class "Default")
      (node (ref "U6") (pin "19") (pinfunction "MAIN_DTR_19") (pintype "unspecified"))
    )
    (net (code "46") (name "M-RI") (class "Default")
      (node (ref "U6") (pin "20") (pinfunction "MAIN_RI_20") (pintype "unspecified"))
    )
    (net (code "47") (name "M-RTS") (class "Default")
      (node (ref "R37") (pin "2") (pinfunction "2_2") (pintype "input"))
      (node (ref "U6") (pin "23") (pinfunction "MAIN_RTS_23") (pintype "unspecified"))
    )
    (net (code "48") (name "M-RXD") (class "Default")
      (node (ref "R33") (pin "1") (pinfunction "1_1") (pintype "input"))
      (node (ref "U6") (pin "17") (pinfunction "MAIN_RXD_17") (pintype "unspecified"))
    )
    (net (code "49") (name "M-TXD") (class "Default")
      (node (ref "R32") (pin "1") (pinfunction "1_1") (pintype "input"))
      (node (ref "U6") (pin "18") (pinfunction "MAIN_TXD_18") (pintype "unspecified"))
    )
    (net (code "50") (name "NET_STATUS") (class "Default")
      (node (ref "R9") (pin "2") (pinfunction "2_2") (pintype "input"))
      (node (ref "U6") (pin "16") (pinfunction "NET_STATUS_16") (pintype "unspecified"))
    )
    (net (code "51") (name "Net-(C42-Pad2)") (class "Default")
      (node (ref "C42") (pin "2") (pinfunction "2_2") (pintype "unspecified"))
      (node (ref "R19") (pin "1") (pinfunction "1_1") (pintype "input"))
    )
    (net (code "52") (name "Net-(C43-Pad2)") (class "Default")
      (node (ref "C43") (pin "2") (pinfunction "2_2") (pintype "unspecified"))
      (node (ref "R20") (pin "1") (pinfunction "1_1") (pintype "input"))
    )
    (net (code "53") (name "Net-(C46-Pad2)") (class "Default")
      (node (ref "C46") (pin "2") (pinfunction "2_2") (pintype "unspecified"))
      (node (ref "R21") (pin "1") (pinfunction "1_1") (pintype "input"))
    )
    (net (code "54") (name "Net-(C47-Pad2)") (class "Default")
      (node (ref "C47") (pin "2") (pinfunction "2_2") (pintype "unspecified"))
      (node (ref "R22") (pin "1") (pinfunction "1_1") (pintype "input"))
    )
    (net (code "55") (name "Net-(C51-Pad2)") (class "Default")
      (node (ref "C51") (pin "2") (pinfunction "2_2") (pintype "unspecified"))
      (node (ref "R24") (pin "1") (pinfunction "1_1") (pintype "input"))
    )
    (net (code "56") (name "Net-(C52-Pad2)") (class "Default")
      (node (ref "C52") (pin "2") (pinfunction "2_2") (pintype "unspecified"))
      (node (ref "R25") (pin "1") (pinfunction "1_1") (pintype "input"))
    )
    (net (code "57") (name "Net-(C56-Pad2)") (class "Default")
      (node (ref "C56") (pin "2") (pinfunction "2_2") (pintype "unspecified"))
      (node (ref "R27") (pin "1") (pinfunction "1_1") (pintype "input"))
    )
    (net (code "58") (name "Net-(C57-Pad2)") (class "Default")
      (node (ref "C57") (pin "2") (pinfunction "2_2") (pintype "unspecified"))
      (node (ref "R28") (pin "1") (pinfunction "1_1") (pintype "input"))
    )
    (net (code "59") (name "Net-(LED1-K)") (class "Default")
      (node (ref "LED1") (pin "1") (pinfunction "K_1") (pintype "input"))
      (node (ref "R10") (pin "2") (pinfunction "2_2") (pintype "input"))
    )
    (net (code "60") (name "Net-(LED2-K)") (class "Default")
      (node (ref "LED2") (pin "1") (pinfunction "K_1") (pintype "input"))
      (node (ref "R13") (pin "2") (pinfunction "2_2") (pintype "input"))
    )
    (net (code "61") (name "Net-(Q1-B)") (class "Default")
      (node (ref "Q1") (pin "1") (pinfunction "B_1") (pintype "unspecified"))
      (node (ref "R9") (pin "1") (pinfunction "1_1") (pintype "input"))
    )
    (net (code "62") (name "Net-(Q1-C)") (class "Default")
      (node (ref "Q1") (pin "3") (pinfunction "C_3") (pintype "unspecified"))
      (node (ref "R10") (pin "1") (pinfunction "1_1") (pintype "input"))
    )
    (net (code "63") (name "Net-(Q2-B)") (class "Default")
      (node (ref "Q2") (pin "1") (pinfunction "B_1") (pintype "unspecified"))
      (node (ref "R11") (pin "1") (pinfunction "1_1") (pintype "input"))
    )
    (net (code "64") (name "Net-(Q2-C)") (class "Default")
      (node (ref "Q2") (pin "3") (pinfunction "C_3") (pintype "unspecified"))
      (node (ref "R13") (pin "1") (pinfunction "1_1") (pintype "input"))
    )
    (net (code "65") (name "Net-(R17-Pad2)") (class "Default")
      (node (ref "R17") (pin "2") (pinfunction "2_2") (pintype "input"))
      (node (ref "U8") (pin "2") (pinfunction "NC_2") (pintype "unspecified"))
    )
    (net (code "66") (name "Net-(RF1-SIG)") (class "Default")
      (node (ref "C31") (pin "2") (pinfunction "2_2") (pintype "input"))
      (node (ref "R15") (pin "2") (pinfunction "2_2") (pintype "input"))
      (node (ref "RF1") (pin "4") (pinfunction "SIG_4") (pintype "unspecified"))
    )
    (net (code "67") (name "Net-(RF2-SIG)") (class "Default")
      (node (ref "C34") (pin "2") (pinfunction "2_2") (pintype "input"))
      (node (ref "L7") (pin "1") (pinfunction "1_1") (pintype "input"))
      (node (ref "R16") (pin "2") (pinfunction "2_2") (pintype "input"))
      (node (ref "RF2") (pin "4") (pinfunction "SIG_4") (pintype "unspecified"))
    )
    (net (code "68") (name "Net-(SPK1-+)") (class "Default")
      (node (ref "C61") (pin "1") (pinfunction "1_1") (pintype "unspecified"))
      (node (ref "L3") (pin "2") (pinfunction "2_2") (pintype "input"))
      (node (ref "SPK1") (pin "1") (pinfunction "+_1") (pintype "input"))
    )
    (net (code "69") (name "Net-(SPK1--)") (class "Default")
      (node (ref "C60") (pin "2") (pinfunction "2_2") (pintype "unspecified"))
      (node (ref "L4") (pin "2") (pinfunction "2_2") (pintype "input"))
      (node (ref "SPK1") (pin "2") (pinfunction "-_2") (pintype "input"))
    )
    (net (code "70") (name "Net-(SPK2-+)") (class "Default")
      (node (ref "C62") (pin "1") (pinfunction "1_1") (pintype "unspecified"))
      (node (ref "L5") (pin "2") (pinfunction "2_2") (pintype "input"))
      (node (ref "SPK2") (pin "1") (pinfunction "+_1") (pintype "input"))
    )
    (net (code "71") (name "Net-(SPK2--)") (class "Default")
      (node (ref "C63") (pin "2") (pinfunction "2_2") (pintype "unspecified"))
      (node (ref "L6") (pin "2") (pinfunction "2_2") (pintype "input"))
      (node (ref "SPK2") (pin "2") (pinfunction "-_2") (pintype "input"))
    )
    (net (code "72") (name "Net-(U1-VDD33)") (class "Default")
      (node (ref "C3") (pin "2") (pinfunction "2_2") (pintype "input"))
      (node (ref "C4") (pin "2") (pinfunction "2_2") (pintype "unspecified"))
      (node (ref "U1") (pin "13") (pinfunction "VDD33_13") (pintype "unspecified"))
    )
    (net (code "73") (name "Net-(U1-XI)") (class "Default")
      (node (ref "C1") (pin "2") (pinfunction "2_2") (pintype "input"))
      (node (ref "U1") (pin "16") (pinfunction "XI_16") (pintype "unspecified"))
      (node (ref "X1") (pin "3") (pinfunction "OSC2_3") (pintype "unspecified"))
    )
    (net (code "74") (name "Net-(U1-XO)") (class "Default")
      (node (ref "C2") (pin "1") (pinfunction "1_1") (pintype "input"))
      (node (ref "U1") (pin "15") (pinfunction "XO_15") (pintype "unspecified"))
      (node (ref "X1") (pin "1") (pinfunction "OSC1_1") (pintype "unspecified"))
    )
    (net (code "75") (name "Net-(U2-VDD33)") (class "Default")
      (node (ref "C11") (pin "2") (pinfunction "2_2") (pintype "input"))
      (node (ref "C12") (pin "2") (pinfunction "2_2") (pintype "unspecified"))
      (node (ref "U2") (pin "13") (pinfunction "VDD33_13") (pintype "unspecified"))
    )
    (net (code "76") (name "Net-(U2-XI)") (class "Default")
      (node (ref "C9") (pin "2") (pinfunction "2_2") (pintype "input"))
      (node (ref "U2") (pin "16") (pinfunction "XI_16") (pintype "unspecified"))
      (node (ref "X2") (pin "3") (pinfunction "OSC2_3") (pintype "unspecified"))
    )
    (net (code "77") (name "Net-(U2-XO)") (class "Default")
      (node (ref "C10") (pin "1") (pinfunction "1_1") (pintype "input"))
      (node (ref "U2") (pin "15") (pinfunction "XO_15") (pintype "unspecified"))
      (node (ref "X2") (pin "1") (pinfunction "OSC1_1") (pintype "unspecified"))
    )
    (net (code "78") (name "Net-(U3-EN)") (class "Default")
      (node (ref "R3") (pin "1") (pinfunction "1_1") (pintype "input"))
      (node (ref "U3") (pin "1") (pinfunction "EN_1") (pintype "input"))
    )
    (net (code "79") (name "Net-(U3-FB)") (class "Default")
      (node (ref "R4") (pin "2") (pinfunction "2_2") (pintype "input"))
      (node (ref "R5") (pin "1") (pinfunction "1_1") (pintype "input"))
      (node (ref "U3") (pin "5") (pinfunction "FB_5") (pintype "input"))
    )
    (net (code "80") (name "Net-(U3-LX)") (class "Default")
      (node (ref "L1") (pin "1") (pinfunction "1_1") (pintype "input"))
      (node (ref "U3") (pin "3") (pinfunction "LX_3") (pintype "input"))
    )
    (net (code "81") (name "Net-(U4-CTS#)") (class "Default")
      (node (ref "R37") (pin "1") (pinfunction "1_1") (pintype "input"))
      (node (ref "U4") (pin "5") (pinfunction "CTS#_5") (pintype "unspecified"))
    )
    (net (code "82") (name "Net-(U4-RTS#)") (class "Default")
      (node (ref "R36") (pin "1") (pinfunction "1_1") (pintype "input"))
      (node (ref "U4") (pin "4") (pinfunction "RTS#_4") (pintype "unspecified"))
    )
    (net (code "83") (name "Net-(U4-RXD)") (class "Default")
      (node (ref "R32") (pin "2") (pinfunction "2_2") (pintype "input"))
      (node (ref "U4") (pin "9") (pinfunction "RXD_9") (pintype "unspecified"))
    )
    (net (code "84") (name "Net-(U4-TXD)") (class "Default")
      (node (ref "R33") (pin "2") (pinfunction "2_2") (pintype "input"))
      (node (ref "U4") (pin "8") (pinfunction "TXD_8") (pintype "unspecified"))
    )
    (net (code "85") (name "Net-(U5-BST)") (class "Default")
      (node (ref "C18") (pin "1") (pinfunction "1_1") (pintype "unspecified"))
      (node (ref "U5") (pin "6") (pinfunction "BST_6") (pintype "input"))
    )
    (net (code "86") (name "Net-(U5-EN)") (class "Default")
      (node (ref "R6") (pin "1") (pinfunction "1_1") (pintype "input"))
      (node (ref "U5") (pin "5") (pinfunction "EN_5") (pintype "input"))
    )
    (net (code "87") (name "Net-(U5-FB)") (class "Default")
      (node (ref "R7") (pin "2") (pinfunction "2_2") (pintype "unspecified"))
      (node (ref "R8") (pin "1") (pinfunction "1_1") (pintype "input"))
      (node (ref "U5") (pin "4") (pinfunction "FB_4") (pintype "input"))
    )
    (net (code "88") (name "Net-(U5-SW)") (class "Default")
      (node (ref "C18") (pin "2") (pinfunction "2_2") (pintype "unspecified"))
      (node (ref "L2") (pin "2") (pinfunction "2_2") (pintype "input"))
      (node (ref "U5") (pin "2") (pinfunction "SW_2") (pintype "input"))
    )
    (net (code "89") (name "Net-(U6-GNSS_ANT)") (class "Default")
      (node (ref "C32") (pin "2") (pinfunction "2_2") (pintype "input"))
      (node (ref "R16") (pin "1") (pinfunction "1_1") (pintype "input"))
      (node (ref "U6") (pin "2") (pinfunction "GNSS_ANT_2") (pintype "unspecified"))
    )
    (net (code "90") (name "Net-(U6-GNSS_VCC)") (class "Default")
      (node (ref "C69") (pin "2") (pinfunction "2_2") (pintype "unspecified"))
      (node (ref "L7") (pin "2") (pinfunction "2_2") (pintype "input"))
      (node (ref "U6") (pin "8") (pinfunction "GNSS_VCC_8") (pintype "unspecified"))
    )
    (net (code "91") (name "Net-(U6-LTE_ANT)") (class "Default")
      (node (ref "C33") (pin "2") (pinfunction "2_2") (pintype "input"))
      (node (ref "R15") (pin "1") (pinfunction "1_1") (pintype "input"))
      (node (ref "U6") (pin "35") (pinfunction "LTE_ANT_35") (pintype "unspecified"))
    )
    (net (code "92") (name "Net-(U7-RXD)") (class "Default")
      (node (ref "R34") (pin "2") (pinfunction "2_2") (pintype "input"))
      (node (ref "U7") (pin "7") (pinfunction "RXD_7") (pintype "unspecified"))
    )
    (net (code "93") (name "Net-(U7-TXD)") (class "Default")
      (node (ref "R35") (pin "2") (pinfunction "2_2") (pintype "input"))
      (node (ref "U7") (pin "6") (pinfunction "TXD_6") (pintype "unspecified"))
    )
    (net (code "94") (name "Net-(U9-AOUTLN)") (class "Default")
      (node (ref "C47") (pin "1") (pinfunction "1_1") (pintype "unspecified"))
      (node (ref "U9") (pin "6") (pinfunction "AOUTLN_6") (pintype "input"))
    )
    (net (code "95") (name "Net-(U9-AOUTLP)") (class "Default")
      (node (ref "C46") (pin "1") (pinfunction "1_1") (pintype "unspecified"))
      (node (ref "U9") (pin "7") (pinfunction "AOUTLP_7") (pintype "input"))
    )
    (net (code "96") (name "Net-(U9-AOUTRN)") (class "Default")
      (node (ref "C43") (pin "1") (pinfunction "1_1") (pintype "unspecified"))
      (node (ref "U9") (pin "10") (pinfunction "AOUTRN_10") (pintype "input"))
    )
    (net (code "97") (name "Net-(U9-AOUTRP)") (class "Default")
      (node (ref "C42") (pin "1") (pinfunction "1_1") (pintype "unspecified"))
      (node (ref "U9") (pin "11") (pinfunction "AOUTRP_11") (pintype "input"))
    )
    (net (code "98") (name "Net-(U9-CAP1)") (class "Default")
      (node (ref "C39") (pin "2") (pinfunction "2_2") (pintype "unspecified"))
      (node (ref "U9") (pin "4") (pinfunction "CAP1_4") (pintype "input"))
    )
    (net (code "99") (name "Net-(U9-CAP2)") (class "Default")
      (node (ref "C40") (pin "2") (pinfunction "2_2") (pintype "unspecified"))
      (node (ref "U9") (pin "5") (pinfunction "CAP2_5") (pintype "input"))
    )
    (net (code "100") (name "Net-(U10-BYPASS)") (class "Default")
      (node (ref "C50") (pin "2") (pinfunction "2_2") (pintype "unspecified"))
      (node (ref "U10") (pin "2") (pinfunction "BYPASS_2") (pintype "unspecified"))
    )
    (net (code "101") (name "Net-(U10-CTRL)") (class "Default")
      (node (ref "R23") (pin "1") (pinfunction "1_1") (pintype "input"))
      (node (ref "U10") (pin "1") (pinfunction "CTRL_1") (pintype "unspecified"))
    )
    (net (code "102") (name "Net-(U10-INN)") (class "Default")
      (node (ref "R25") (pin "2") (pinfunction "2_2") (pintype "input"))
      (node (ref "U10") (pin "4") (pinfunction "INN_4") (pintype "unspecified"))
    )
    (net (code "103") (name "Net-(U10-INP)") (class "Default")
      (node (ref "R24") (pin "2") (pinfunction "2_2") (pintype "input"))
      (node (ref "U10") (pin "3") (pinfunction "INP_3") (pintype "unspecified"))
    )
    (net (code "104") (name "Net-(U10-VON)") (class "Default")
      (node (ref "L4") (pin "1") (pinfunction "1_1") (pintype "input"))
      (node (ref "U10") (pin "5") (pinfunction "VON_5") (pintype "unspecified"))
    )
    (net (code "105") (name "Net-(U10-VOP)") (class "Default")
      (node (ref "L3") (pin "1") (pinfunction "1_1") (pintype "input"))
      (node (ref "U10") (pin "8") (pinfunction "VOP_8") (pintype "unspecified"))
    )
    (net (code "106") (name "Net-(U11-BYPASS)") (class "Default")
      (node (ref "C55") (pin "2") (pinfunction "2_2") (pintype "unspecified"))
      (node (ref "U11") (pin "2") (pinfunction "BYPASS_2") (pintype "unspecified"))
    )
    (net (code "107") (name "Net-(U11-CTRL)") (class "Default")
      (node (ref "R26") (pin "1") (pinfunction "1_1") (pintype "input"))
      (node (ref "U11") (pin "1") (pinfunction "CTRL_1") (pintype "unspecified"))
    )
    (net (code "108") (name "Net-(U11-INN)") (class "Default")
      (node (ref "R28") (pin "2") (pinfunction "2_2") (pintype "input"))
      (node (ref "U11") (pin "4") (pinfunction "INN_4") (pintype "unspecified"))
    )
    (net (code "109") (name "Net-(U11-INP)") (class "Default")
      (node (ref "R27") (pin "2") (pinfunction "2_2") (pintype "input"))
      (node (ref "U11") (pin "3") (pinfunction "INP_3") (pintype "unspecified"))
    )
    (net (code "110") (name "Net-(U11-VON)") (class "Default")
      (node (ref "L6") (pin "1") (pinfunction "1_1") (pintype "input"))
      (node (ref "U11") (pin "5") (pinfunction "VON_5") (pintype "unspecified"))
    )
    (net (code "111") (name "Net-(U11-VOP)") (class "Default")
      (node (ref "L5") (pin "1") (pinfunction "1_1") (pintype "input"))
      (node (ref "U11") (pin "8") (pinfunction "VOP_8") (pintype "unspecified"))
    )
    (net (code "112") (name "Net-(USB1-CC1)") (class "Default")
      (node (ref "R2") (pin "1") (pinfunction "1_1") (pintype "input"))
      (node (ref "USB1") (pin "4") (pinfunction "CC1_4") (pintype "unspecified"))
    )
    (net (code "113") (name "Net-(USB1-CC2)") (class "Default")
      (node (ref "R1") (pin "1") (pinfunction "1_1") (pintype "input"))
      (node (ref "USB1") (pin "10") (pinfunction "CC2_10") (pintype "unspecified"))
    )
    (net (code "114") (name "R-SPKN") (class "Default")
      (node (ref "C45") (pin "2") (pinfunction "2_2") (pintype "input"))
      (node (ref "C57") (pin "1") (pinfunction "1_1") (pintype "unspecified"))
      (node (ref "R20") (pin "2") (pinfunction "2_2") (pintype "input"))
    )
    (net (code "115") (name "R-SPKP") (class "Default")
      (node (ref "C44") (pin "1") (pinfunction "1_1") (pintype "input"))
      (node (ref "C56") (pin "1") (pinfunction "1_1") (pintype "unspecified"))
      (node (ref "R19") (pin "2") (pinfunction "2_2") (pintype "input"))
    )
    (net (code "116") (name "RESET_N") (class "Default")
      (node (ref "C23") (pin "2") (pinfunction "2_2") (pintype "unspecified"))
      (node (ref "R12") (pin "2") (pinfunction "2_2") (pintype "input"))
      (node (ref "SW1") (pin "1") (pinfunction "1_1") (pintype "input"))
      (node (ref "U6") (pin "15") (pinfunction "RESET_N_15") (pintype "unspecified"))
    )
    (net (code "117") (name "SIM1-CLK") (class "Default")
      (node (ref "C66") (pin "1") (pinfunction "1_1") (pintype "input"))
      (node (ref "SIM1") (pin "3") (pinfunction "CLK_3") (pintype "unspecified"))
      (node (ref "U6") (pin "13") (pinfunction "USIM_CLK_13") (pintype "unspecified"))
    )
    (net (code "118") (name "SIM1-DATA") (class "Default")
      (node (ref "C67") (pin "1") (pinfunction "1_1") (pintype "input"))
      (node (ref "SIM1") (pin "7") (pinfunction "I/O_7") (pintype "unspecified"))
      (node (ref "U6") (pin "11") (pinfunction "USIM_DATA_11") (pintype "unspecified"))
    )
    (net (code "119") (name "SIM1-DET") (class "Default")
      (node (ref "R29") (pin "2") (pinfunction "2_2") (pintype "input"))
      (node (ref "SIM1") (pin "8") (pinfunction "CD_8") (pintype "unspecified"))
      (node (ref "U6") (pin "79") (pinfunction "USIM_DET_79") (pintype "unspecified"))
    )
    (net (code "120") (name "SIM1-RST") (class "Default")
      (node (ref "C65") (pin "1") (pinfunction "1_1") (pintype "input"))
      (node (ref "SIM1") (pin "2") (pinfunction "RST_2") (pintype "unspecified"))
      (node (ref "U6") (pin "12") (pinfunction "USIM_RST_12") (pintype "unspecified"))
    )
    (net (code "121") (name "SIM1-VDD") (class "Default")
      (node (ref "C64") (pin "1") (pinfunction "1_1") (pintype "input"))
      (node (ref "C68") (pin "1") (pinfunction "1_1") (pintype "unspecified"))
      (node (ref "SIM1") (pin "1") (pinfunction "VCC_1") (pintype "unspecified"))
      (node (ref "U6") (pin "14") (pinfunction "USIM_VDD_14") (pintype "unspecified"))
    )
    (net (code "122") (name "SIM2-CLK") (class "Default")
      (node (ref "U6") (pin "62") (pinfunction "USIM2_CLK_62") (pintype "unspecified"))
      (node (ref "U8") (pin "6") (pinfunction "CLK_6") (pintype "unspecified"))
    )
    (net (code "123") (name "SIM2-DAT") (class "Default")
      (node (ref "R17") (pin "1") (pinfunction "1_1") (pintype "input"))
      (node (ref "R18") (pin "1") (pinfunction "1_1") (pintype "input"))
      (node (ref "U6") (pin "64") (pinfunction "USIM2_DAT_64") (pintype "unspecified"))
      (node (ref "U8") (pin "3") (pinfunction "IO_3") (pintype "unspecified"))
    )
    (net (code "124") (name "SIM2-RST") (class "Default")
      (node (ref "U6") (pin "63") (pinfunction "USIM2_RST_63") (pintype "unspecified"))
      (node (ref "U8") (pin "7") (pinfunction "RST#_7") (pintype "unspecified"))
    )
    (net (code "125") (name "SIM2-VDD") (class "Default")
      (node (ref "C37") (pin "2") (pinfunction "2_2") (pintype "input"))
      (node (ref "C38") (pin "2") (pinfunction "2_2") (pintype "unspecified"))
      (node (ref "R18") (pin "2") (pinfunction "2_2") (pintype "input"))
      (node (ref "U6") (pin "65") (pinfunction "USIM2_VDD_65") (pintype "unspecified"))
      (node (ref "U8") (pin "8") (pinfunction "VCC_8") (pintype "unspecified"))
    )
    (net (code "126") (name "STATUS") (class "Default")
      (node (ref "R11") (pin "2") (pinfunction "2_2") (pintype "input"))
      (node (ref "U6") (pin "25") (pinfunction "STATUS_25") (pintype "unspecified"))
    )
    (net (code "127") (name "USB-VBUS") (class "Default")
      (node (ref "C13") (pin "2") (pinfunction "2_2") (pintype "input"))
      (node (ref "C14") (pin "2") (pinfunction "2_2") (pintype "unspecified"))
      (node (ref "C17") (pin "2") (pinfunction "2_2") (pintype "input"))
      (node (ref "C20") (pin "1") (pinfunction "1_1") (pintype "input"))
      (node (ref "C5") (pin "2") (pinfunction "2_2") (pintype "input"))
      (node (ref "C6") (pin "2") (pinfunction "2_2") (pintype "unspecified"))
      (node (ref "C7") (pin "1") (pinfunction "1_1") (pintype "input"))
      (node (ref "C8") (pin "1") (pinfunction "1_1") (pintype "input"))
      (node (ref "R3") (pin "2") (pinfunction "2_2") (pintype "input"))
      (node (ref "R6") (pin "2") (pinfunction "2_2") (pintype "input"))
      (node (ref "U1") (pin "12") (pinfunction "V5_12") (pintype "unspecified"))
      (node (ref "U2") (pin "12") (pinfunction "V5_12") (pintype "unspecified"))
      (node (ref "U3") (pin "4") (pinfunction "IN_4") (pintype "input"))
      (node (ref "U5") (pin "3") (pinfunction "VIN_3") (pintype "input"))
      (node (ref "U6") (pin "61") (pinfunction "VBUS_61") (pintype "unspecified"))
      (node (ref "USB1") (pin "11") (pinfunction "VBUS_11") (pintype "unspecified"))
      (node (ref "USB1") (pin "2") (pinfunction "VBUS_2") (pintype "unspecified"))
      (node (ref "USB2") (pin "1") (pinfunction "VCC_1") (pintype "unspecified"))
      (node (ref "USB2") (pin "5") (pinfunction "VCC_5") (pintype "unspecified"))
      (node (ref "USB3") (pin "1") (pinfunction "VCC_1") (pintype "unspecified"))
      (node (ref "USB3") (pin "5") (pinfunction "VCC_5") (pintype "unspecified"))
    )
    (net (code "128") (name "USB_BOOT") (class "Default")
      (node (ref "C24") (pin "2") (pinfunction "2_2") (pintype "unspecified"))
      (node (ref "R14") (pin "2") (pinfunction "2_2") (pintype "input"))
      (node (ref "SW2") (pin "1") (pinfunction "1_1") (pintype "input"))
      (node (ref "U6") (pin "82") (pinfunction "USB_BOOT_82") (pintype "unspecified"))
    )
    (net (code "129") (name "VBAT") (class "Default")
      (node (ref "C19") (pin "1") (pinfunction "1_1") (pintype "input"))
      (node (ref "C25") (pin "2") (pinfunction "2_2") (pintype "input"))
      (node (ref "C26") (pin "2") (pinfunction "2_2") (pintype "unspecified"))
      (node (ref "C27") (pin "2") (pinfunction "2_2") (pintype "input"))
      (node (ref "C28") (pin "2") (pinfunction "2_2") (pintype "input"))
      (node (ref "C29") (pin "2") (pinfunction "2_2") (pintype "unspecified"))
      (node (ref "C30") (pin "2") (pinfunction "2_2") (pintype "input"))
      (node (ref "L2") (pin "1") (pinfunction "1_1") (pintype "input"))
      (node (ref "R7") (pin "1") (pinfunction "1_1") (pintype "unspecified"))
      (node (ref "U6") (pin "42") (pinfunction "VBAT_42") (pintype "unspecified"))
      (node (ref "U6") (pin "43") (pinfunction "VBAT_43") (pintype "unspecified"))
    )
    (net (code "130") (name "unconnected-(SIM1-VPP-Pad6)") (class "Default")
      (node (ref "SIM1") (pin "6") (pinfunction "VPP_6") (pintype "unspecified+no_connect"))
    )
    (net (code "131") (name "unconnected-(U1-RESET#{slash}CDP-Pad9)") (class "Default")
      (node (ref "U1") (pin "9") (pinfunction "RESET#/CDP_9") (pintype "unspecified+no_connect"))
    )
    (net (code "132") (name "unconnected-(U2-RESET#{slash}CDP-Pad9)") (class "Default")
      (node (ref "U2") (pin "9") (pinfunction "RESET#/CDP_9") (pintype "unspecified+no_connect"))
    )
    (net (code "133") (name "unconnected-(U4-TNOW{slash}DTR#-Pad6)") (class "Default")
      (node (ref "U4") (pin "6") (pinfunction "TNOW/DTR#_6") (pintype "unspecified+no_connect"))
    )
    (net (code "134") (name "unconnected-(U6-1PPS-Pad108)") (class "Default")
      (node (ref "U6") (pin "108") (pinfunction "1PPS_108") (pintype "unspecified+no_connect"))
    )
    (net (code "135") (name "unconnected-(U6-AGPIO3-Pad99)") (class "Default")
      (node (ref "U6") (pin "99") (pinfunction "AGPIO3_99") (pintype "unspecified+no_connect"))
    )
    (net (code "136") (name "unconnected-(U6-GNSS_RXD-Pad29)") (class "Default")
      (node (ref "U6") (pin "29") (pinfunction "GNSS_RXD_29") (pintype "unspecified+no_connect"))
    )
    (net (code "137") (name "unconnected-(U6-GNSS_TXD-Pad28)") (class "Default")
      (node (ref "U6") (pin "28") (pinfunction "GNSS_TXD_28") (pintype "unspecified+no_connect"))
    )
    (net (code "138") (name "unconnected-(U6-LDO_CTL-Pad97)") (class "Default")
      (node (ref "U6") (pin "97") (pinfunction "LDO_CTL_97") (pintype "unspecified+no_connect"))
    )
    (net (code "139") (name "unconnected-(U6-RESERVED-Pad3)") (class "Default")
      (node (ref "U6") (pin "3") (pinfunction "RESERVED_3") (pintype "unspecified+no_connect"))
    )
    (net (code "140") (name "unconnected-(U6-RESERVED-Pad4)") (class "Default")
      (node (ref "U6") (pin "4") (pinfunction "RESERVED_4") (pintype "unspecified+no_connect"))
    )
    (net (code "141") (name "unconnected-(U6-RESERVED-Pad5)") (class "Default")
      (node (ref "U6") (pin "5") (pinfunction "RESERVED_5") (pintype "unspecified+no_connect"))
    )
    (net (code "142") (name "unconnected-(U6-RESERVED-Pad6)") (class "Default")
      (node (ref "U6") (pin "6") (pinfunction "RESERVED_6") (pintype "unspecified+no_connect"))
    )
    (net (code "143") (name "unconnected-(U6-RESERVED-Pad44)") (class "Default")
      (node (ref "U6") (pin "44") (pinfunction "RESERVED_44") (pintype "unspecified+no_connect"))
    )
    (net (code "144") (name "unconnected-(U6-RESERVED-Pad54)") (class "Default")
      (node (ref "U6") (pin "54") (pinfunction "RESERVED_54") (pintype "unspecified+no_connect"))
    )
    (net (code "145") (name "unconnected-(U6-RESERVED-Pad55)") (class "Default")
      (node (ref "U6") (pin "55") (pinfunction "RESERVED_55") (pintype "unspecified+no_connect"))
    )
    (net (code "146") (name "unconnected-(U6-RESERVED-Pad56)") (class "Default")
      (node (ref "U6") (pin "56") (pinfunction "RESERVED_56") (pintype "unspecified+no_connect"))
    )
    (net (code "147") (name "unconnected-(U6-RESERVED-Pad57)") (class "Default")
      (node (ref "U6") (pin "57") (pinfunction "RESERVED_57") (pintype "unspecified+no_connect"))
    )
    (net (code "148") (name "unconnected-(U6-RESERVED-Pad58)") (class "Default")
      (node (ref "U6") (pin "58") (pinfunction "RESERVED_58") (pintype "unspecified+no_connect"))
    )
    (net (code "149") (name "unconnected-(U6-RESERVED-Pad68)") (class "Default")
      (node (ref "U6") (pin "68") (pinfunction "RESERVED_68") (pintype "unspecified+no_connect"))
    )
    (net (code "150") (name "unconnected-(U6-RESERVED-Pad69)") (class "Default")
      (node (ref "U6") (pin "69") (pinfunction "RESERVED_69") (pintype "unspecified+no_connect"))
    )
    (net (code "151") (name "unconnected-(U6-RESERVED-Pad74)") (class "Default")
      (node (ref "U6") (pin "74") (pinfunction "RESERVED_74") (pintype "unspecified+no_connect"))
    )
    (net (code "152") (name "unconnected-(U6-RESERVED-Pad75)") (class "Default")
      (node (ref "U6") (pin "75") (pinfunction "RESERVED_75") (pintype "unspecified+no_connect"))
    )
    (net (code "153") (name "unconnected-(U6-RESERVED-Pad76)") (class "Default")
      (node (ref "U6") (pin "76") (pinfunction "RESERVED_76") (pintype "unspecified+no_connect"))
    )
    (net (code "154") (name "unconnected-(U6-RESERVED-Pad77)") (class "Default")
      (node (ref "U6") (pin "77") (pinfunction "RESERVED_77") (pintype "unspecified+no_connect"))
    )
    (net (code "155") (name "unconnected-(U6-RESERVED-Pad80)") (class "Default")
      (node (ref "U6") (pin "80") (pinfunction "RESERVED_80") (pintype "unspecified+no_connect"))
    )
    (net (code "156") (name "unconnected-(U6-RESERVED-Pad81)") (class "Default")
      (node (ref "U6") (pin "81") (pinfunction "RESERVED_81") (pintype "unspecified+no_connect"))
    )
    (net (code "157") (name "unconnected-(U6-RESERVED-Pad83)") (class "Default")
      (node (ref "U6") (pin "83") (pinfunction "RESERVED_83") (pintype "unspecified+no_connect"))
    )
    (net (code "158") (name "unconnected-(U6-RESERVED-Pad84)") (class "Default")
      (node (ref "U6") (pin "84") (pinfunction "RESERVED_84") (pintype "unspecified+no_connect"))
    )
    (net (code "159") (name "unconnected-(U6-RESERVED-Pad85)") (class "Default")
      (node (ref "U6") (pin "85") (pinfunction "RESERVED_85") (pintype "unspecified+no_connect"))
    )
    (net (code "160") (name "unconnected-(U6-RESERVED-Pad86)") (class "Default")
      (node (ref "U6") (pin "86") (pinfunction "RESERVED_86") (pintype "unspecified+no_connect"))
    )
    (net (code "161") (name "unconnected-(U6-RESERVED-Pad87)") (class "Default")
      (node (ref "U6") (pin "87") (pinfunction "RESERVED_87") (pintype "unspecified+no_connect"))
    )
    (net (code "162") (name "unconnected-(U6-RESERVED-Pad98)") (class "Default")
      (node (ref "U6") (pin "98") (pinfunction "RESERVED_98") (pintype "unspecified+no_connect"))
    )
    (net (code "163") (name "unconnected-(U6-RESERVED-Pad103)") (class "Default")
      (node (ref "U6") (pin "103") (pinfunction "RESERVED_103") (pintype "unspecified+no_connect"))
    )
    (net (code "164") (name "unconnected-(U6-RESERVED-Pad104)") (class "Default")
      (node (ref "U6") (pin "104") (pinfunction "RESERVED_104") (pintype "unspecified+no_connect"))
    )
    (net (code "165") (name "unconnected-(U6-RESERVED-Pad105)") (class "Default")
      (node (ref "U6") (pin "105") (pinfunction "RESERVED_105") (pintype "unspecified+no_connect"))
    )
    (net (code "166") (name "unconnected-(U6-RESERVED-Pad109)") (class "Default")
      (node (ref "U6") (pin "109") (pinfunction "RESERVED_109") (pintype "unspecified+no_connect"))
    )
    (net (code "167") (name "unconnected-(U6-VDD_EXT-Pad24)") (class "Default")
      (node (ref "U6") (pin "24") (pinfunction "VDD_EXT_24") (pintype "unspecified+no_connect"))
    )
    (net (code "168") (name "unconnected-(U6-WAKEUP0-Pad101)") (class "Default")
      (node (ref "U6") (pin "101") (pinfunction "WAKEUP0_101") (pintype "unspecified+no_connect"))
    )
    (net (code "169") (name "unconnected-(U7-RTS#-Pad4)") (class "Default")
      (node (ref "U7") (pin "4") (pinfunction "RTS#_4") (pintype "unspecified+no_connect"))
    )
    (net (code "170") (name "unconnected-(U8-NC-Pad4)") (class "Default")
      (node (ref "U8") (pin "4") (pinfunction "NC_4") (pintype "unspecified+no_connect"))
    )
    (net (code "171") (name "unconnected-(U8-NC-Pad5)") (class "Default")
      (node (ref "U8") (pin "5") (pinfunction "NC_5") (pintype "unspecified+no_connect"))
    )
    (net (code "172") (name "unconnected-(U12-NC-Pad1)") (class "Default")
      (node (ref "U12") (pin "1") (pinfunction "NC_1") (pintype "unspecified+no_connect"))
    )
    (net (code "173") (name "unconnected-(U12-NC-Pad6)") (class "Default")
      (node (ref "U12") (pin "6") (pinfunction "NC_6") (pintype "unspecified+no_connect"))
    )
    (net (code "174") (name "unconnected-(USB1-SBU1-Pad9)") (class "Default")
      (node (ref "USB1") (pin "9") (pinfunction "SBU1_9") (pintype "unspecified+no_connect"))
    )
    (net (code "175") (name "unconnected-(USB1-SBU2-Pad3)") (class "Default")
      (node (ref "USB1") (pin "3") (pinfunction "SBU2_3") (pintype "unspecified+no_connect"))
    )
  )
)
